# electrosteel2020_10_arrange7_synthboards.net
KiCad netlist of a schematic drawn in EAGLE
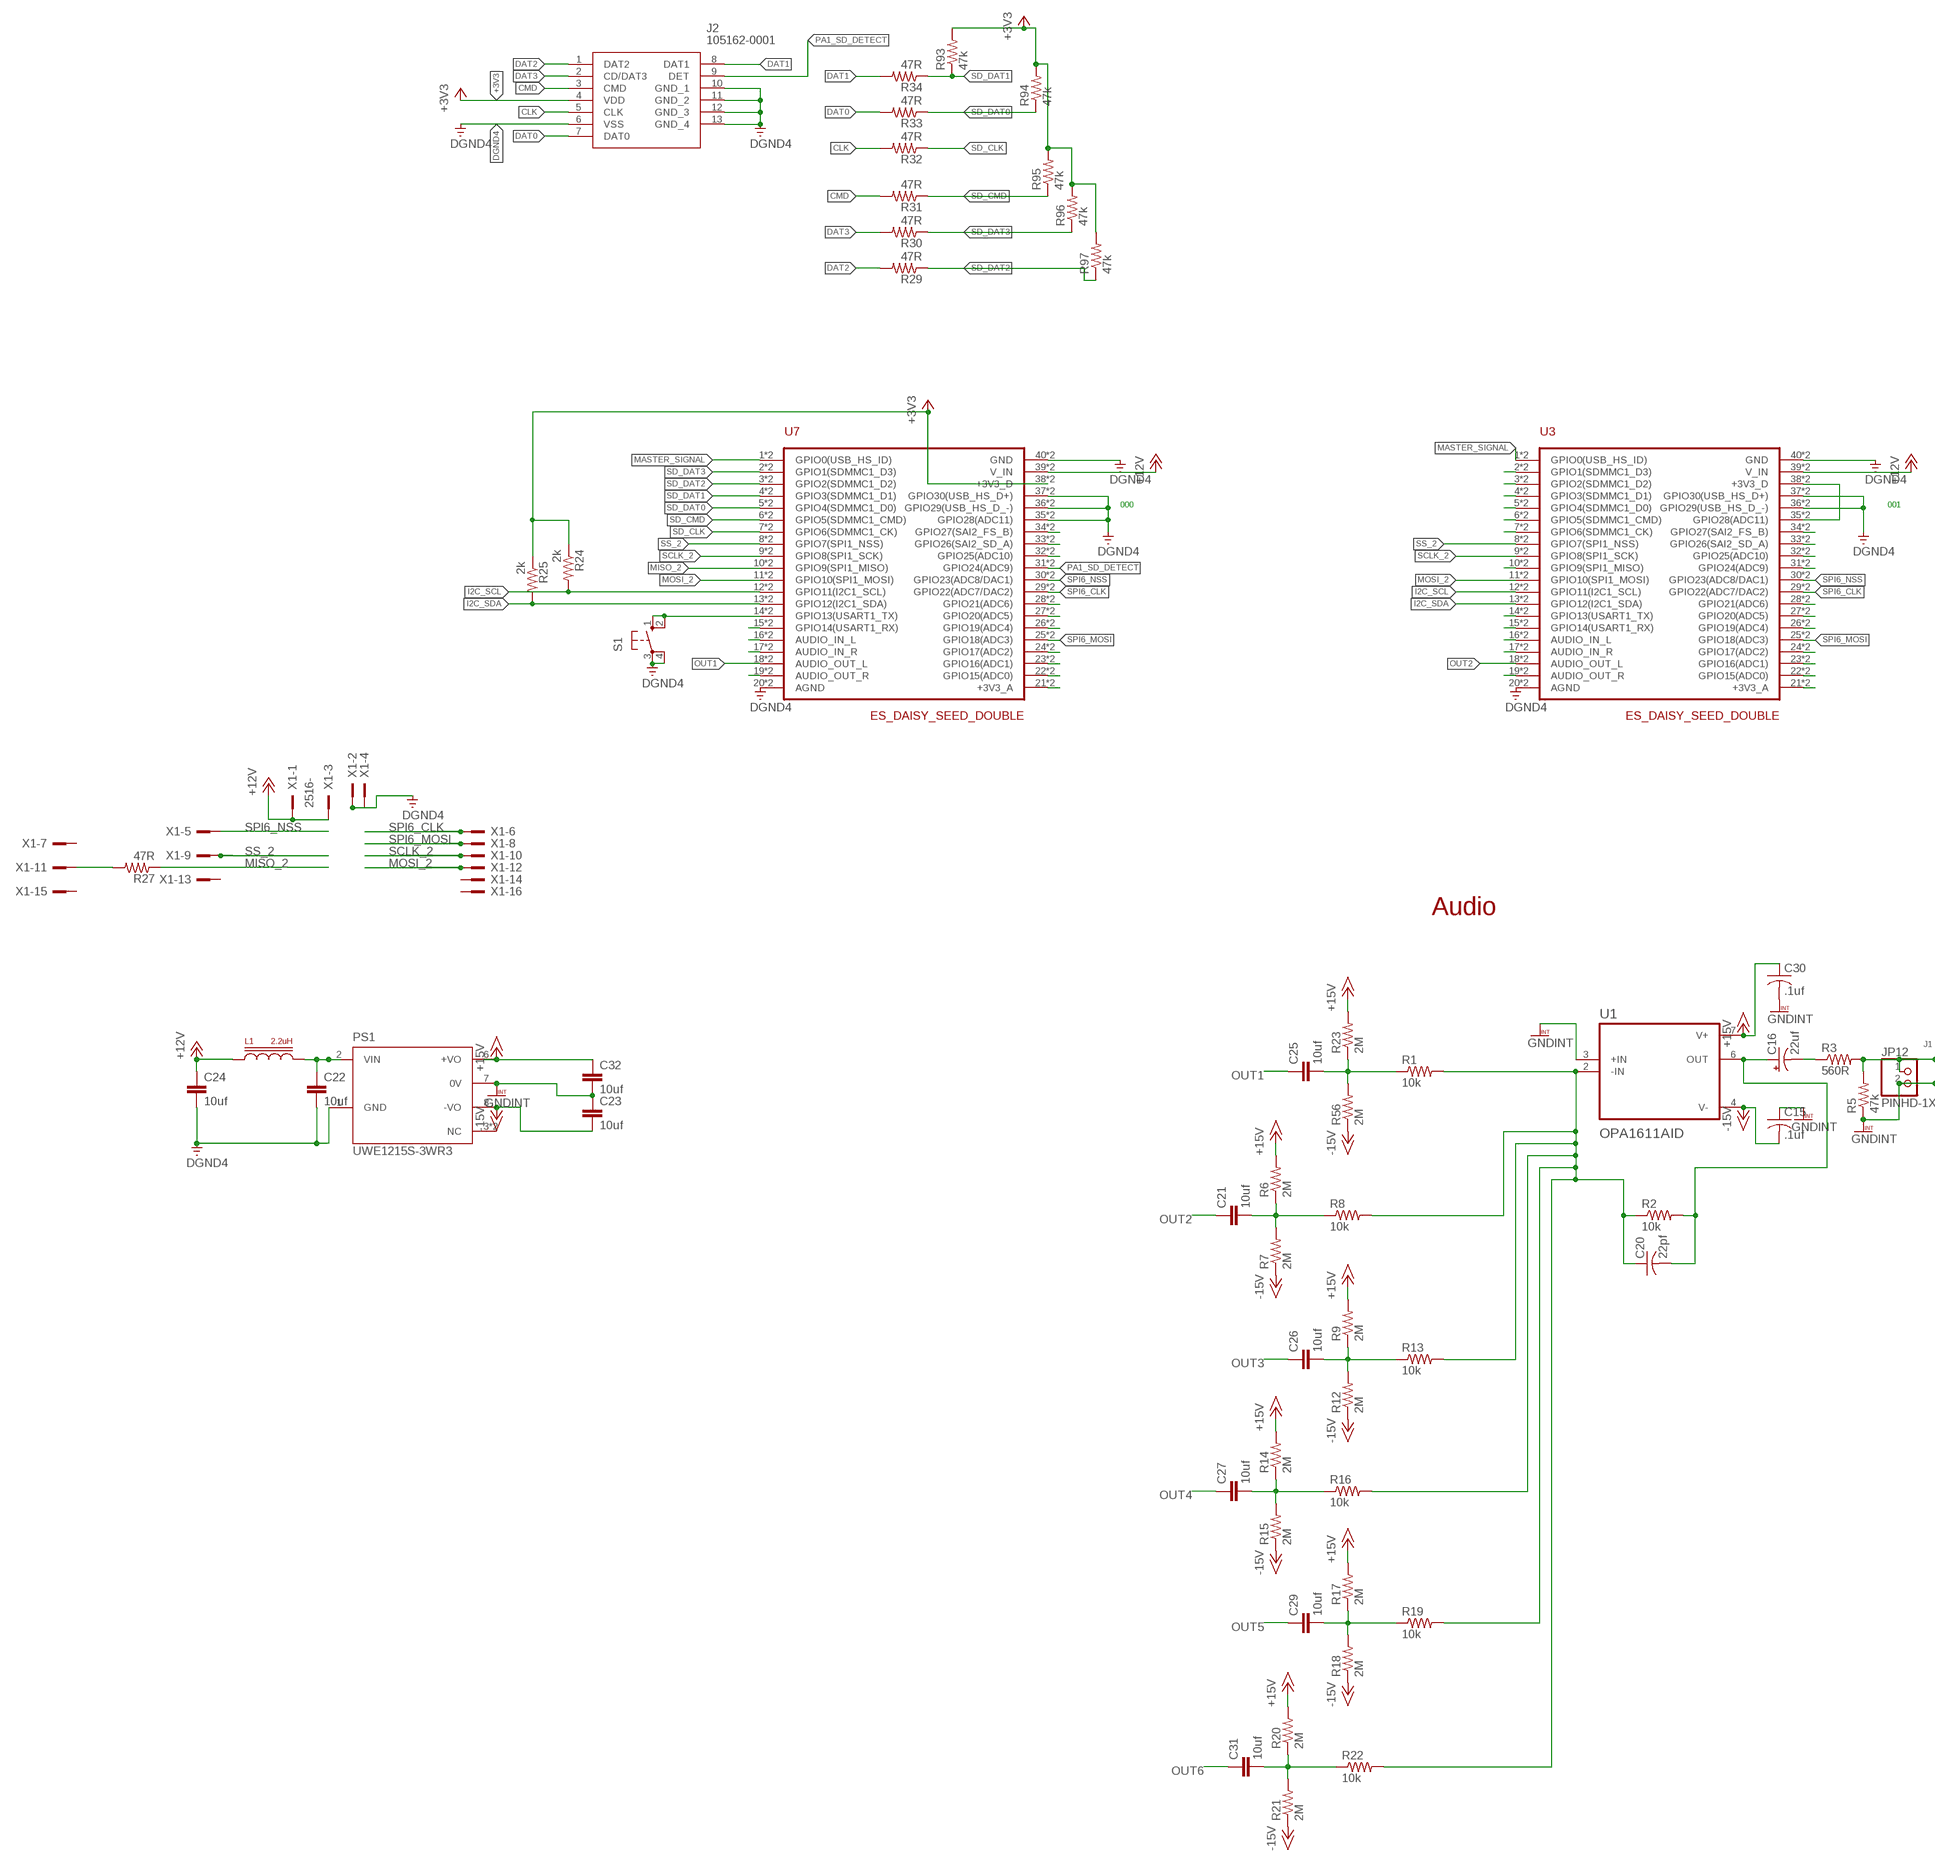
[diagram p0: schematic, sheet 1, part 1 of 3]
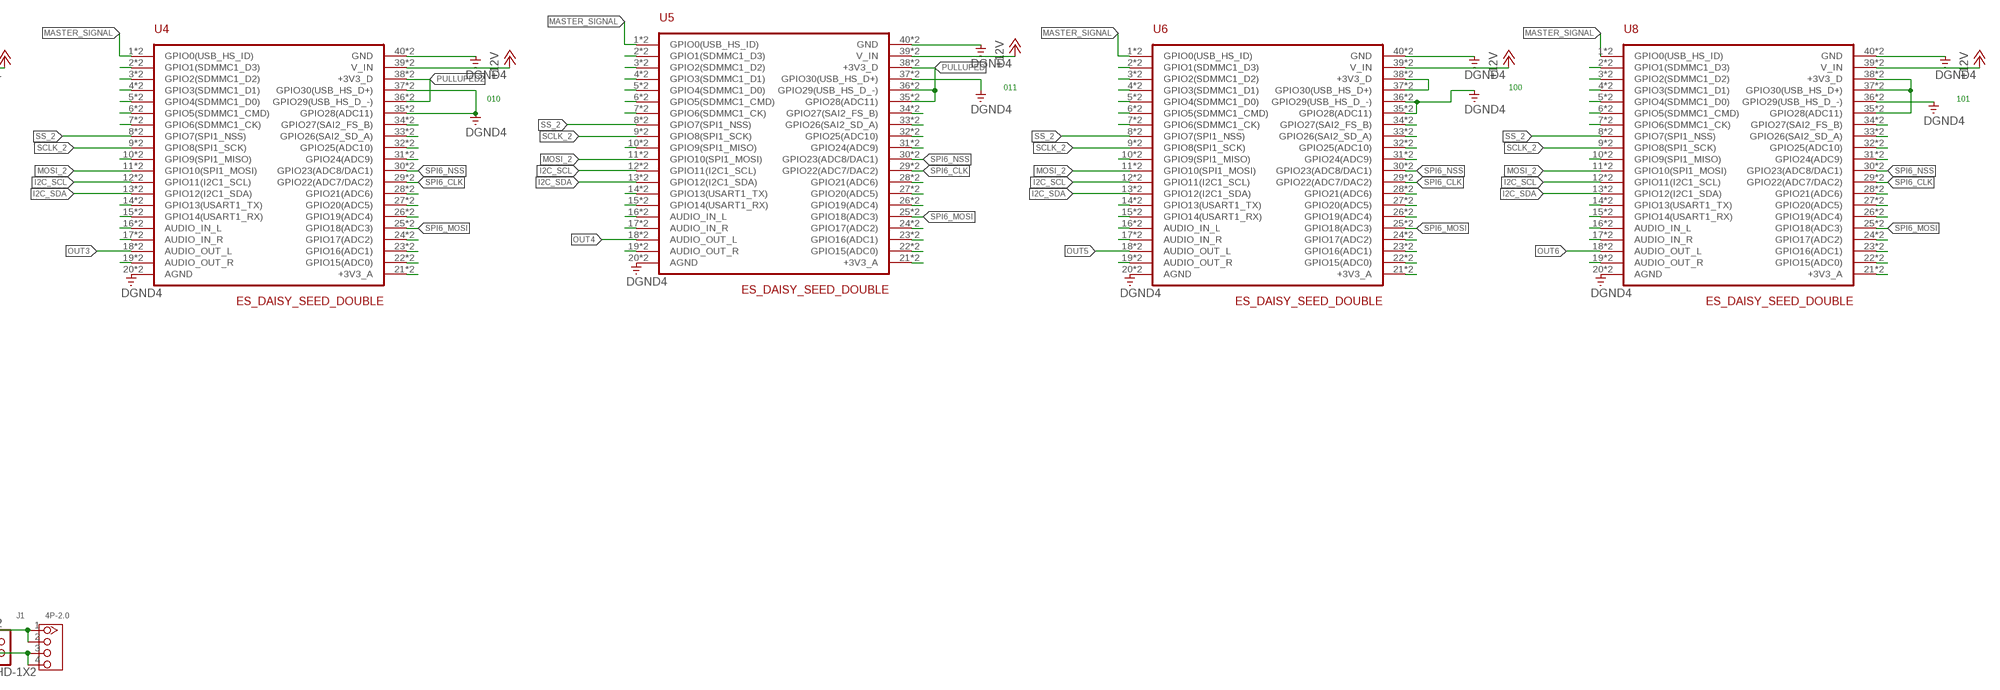
[diagram p1: schematic, sheet 1, part 2 of 3]
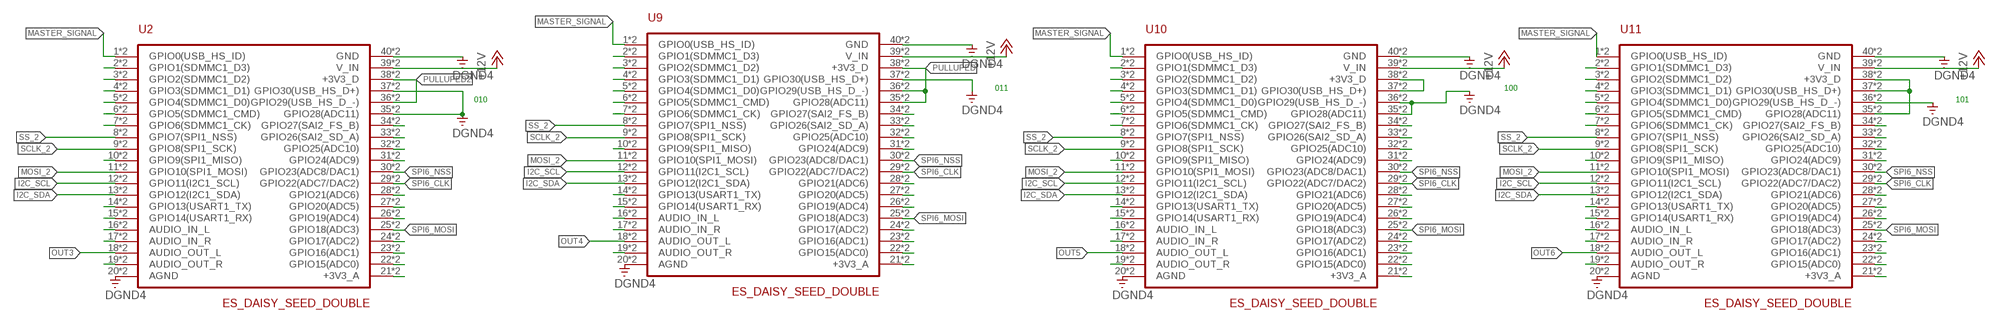
[diagram p2: schematic, sheet 1, part 3 of 3]

(export (version "E")
  (design (tool "Eeschema 10.0.6"))
  (components
    (comp (ref "C15")
      (value ".1uf")
      (footprint "eagle-import:C0603K")
      (fields (field (name "PARTNO") "CC0603KRX7R8BB104"))
      (libsource (lib "eagle-import") (part "C-USC0603K"))
    )
    (comp (ref "C16")
      (value "22uf")
      (footprint "eagle-import:PANASONIC_D")
      (fields (field (name "PARTNO") "EEE-1CA220NP"))
      (libsource (lib "eagle-import") (part "CPOL-USD"))
    )
    (comp (ref "C20")
      (value "22pf")
      (footprint "eagle-import:C0603")
      (fields (field (name "PARTNO") "CC0603JRNPO9BN220"))
      (libsource (lib "eagle-import") (part "rcl_334_C-USC0603"))
    )
    (comp (ref "C21")
      (value "10uf")
      (footprint "eagle-import:C1206K")
      (fields (field (name "PARTNO") "TMK316F106ZL-T"))
      (libsource (lib "eagle-import") (part "C-EUC1206K"))
    )
    (comp (ref "C22")
      (value "10uf")
      (footprint "eagle-import:C1206K")
      (fields (field (name "PARTNO") "TMK316F106ZL-T"))
      (libsource (lib "eagle-import") (part "C-EUC1206K"))
    )
    (comp (ref "C23")
      (value "10uf")
      (footprint "eagle-import:C1206K")
      (fields (field (name "PARTNO") "TMK316F106ZL-T"))
      (libsource (lib "eagle-import") (part "C-EUC1206K"))
    )
    (comp (ref "C24")
      (value "10uf")
      (footprint "eagle-import:C1206K")
      (fields (field (name "PARTNO") "TMK316F106ZL-T"))
      (libsource (lib "eagle-import") (part "C-EUC1206K"))
    )
    (comp (ref "C25")
      (value "10uf")
      (footprint "eagle-import:C1206K")
      (fields (field (name "PARTNO") "TMK316F106ZL-T"))
      (libsource (lib "eagle-import") (part "C-EUC1206K"))
    )
    (comp (ref "C26")
      (value "10uf")
      (footprint "eagle-import:C1206K")
      (fields (field (name "PARTNO") "TMK316F106ZL-T"))
      (libsource (lib "eagle-import") (part "C-EUC1206K"))
    )
    (comp (ref "C27")
      (value "10uf")
      (footprint "eagle-import:C1206K")
      (fields (field (name "PARTNO") "TMK316F106ZL-T"))
      (libsource (lib "eagle-import") (part "C-EUC1206K"))
    )
    (comp (ref "C29")
      (value "10uf")
      (footprint "eagle-import:C1206K")
      (fields (field (name "PARTNO") "TMK316F106ZL-T"))
      (libsource (lib "eagle-import") (part "C-EUC1206K"))
    )
    (comp (ref "C30")
      (value ".1uf")
      (footprint "eagle-import:C0603K")
      (fields (field (name "PARTNO") "CC0603KRX7R8BB104"))
      (libsource (lib "eagle-import") (part "C-USC0603K"))
    )
    (comp (ref "C31")
      (value "10uf")
      (footprint "eagle-import:C1206K")
      (fields (field (name "PARTNO") "TMK316F106ZL-T"))
      (libsource (lib "eagle-import") (part "C-EUC1206K"))
    )
    (comp (ref "C32")
      (value "10uf")
      (footprint "eagle-import:C1206K")
      (fields (field (name "PARTNO") "TMK316F106ZL-T"))
      (libsource (lib "eagle-import") (part "C-EUC1206K"))
    )
    (comp (ref "J1")
      (value "4P-2.0")
      (footprint "eagle-import:HW4-2.0")
      (fields (field (name "PARTNO") "110990030"))
      (libsource (lib "eagle-import") (part "GROVE-CONNECTOR-DIP(4P-2.0)"))
    )
    (comp (ref "J2")
      (value "105162-0001")
      (footprint "eagle-import:105162-0001")
      (fields (field (name "MF") "Molex") (field (name "MP") "1051620001"))
      (libsource (lib "eagle-import") (part "105162-0001"))
    )
    (comp (ref "JP12")
      (value "PINHD-1X2")
      (footprint "eagle-import:1X02")
      (fields (field (name "PARTNO") "*DNP"))
      (libsource (lib "eagle-import") (part "PINHD-1X2"))
    )
    (comp (ref "L1")
      (value "2.2uH")
      (footprint "eagle-import:BOURNS_SRP2010")
      (fields (field (name "PARTNO") "SRP2010-2R2M"))
      (libsource (lib "eagle-import") (part "INDUCTORS"))
    )
    (comp (ref "PS1")
      (value "UWE1215S-3WR3")
      (footprint "eagle-import:CONV_UWE1215S-3WR3")
      (fields
        (field (name "DIGI-KEY_PART_NUMBER") "2725-UWE1215S-3WR3-ND")
        (field (name "MF") "Mornsun America, LLC")
      )
      (libsource (lib "eagle-import") (part "UWE1215S-3WR3"))
    )
    (comp (ref "R1")
      (value "10k")
      (footprint "eagle-import:R0603")
      (fields (field (name "PARTNO") "ESR03EZPF1002"))
      (libsource (lib "eagle-import") (part "Resistor_16378527_R-US_R0603"))
    )
    (comp (ref "R2")
      (value "10k")
      (footprint "eagle-import:R0603")
      (fields (field (name "PARTNO") "ESR03EZPF1002"))
      (libsource (lib "eagle-import") (part "Resistor_16378527_R-US_R0603"))
    )
    (comp (ref "R3")
      (value "560R")
      (footprint "eagle-import:R0603")
      (fields (field (name "PARTNO") "ESR03EZPF5600"))
      (libsource (lib "eagle-import") (part "Resistor_16378527_R-US_R0603"))
    )
    (comp (ref "R5")
      (value "47k")
      (footprint "eagle-import:R0603")
      (fields (field (name "PARTNO") "ESR03EZPJ473"))
      (libsource (lib "eagle-import") (part "Resistor_16378527_R-US_R0603"))
    )
    (comp (ref "R6")
      (value "2M")
      (footprint "eagle-import:R0603")
      (fields (field (name "PARTNO") "RMCF0603FT2M00"))
      (libsource (lib "eagle-import") (part "R-US_R0603"))
    )
    (comp (ref "R7")
      (value "2M")
      (footprint "eagle-import:R0603")
      (fields (field (name "PARTNO") "RMCF0603FT2M00"))
      (libsource (lib "eagle-import") (part "R-US_R0603"))
    )
    (comp (ref "R8")
      (value "10k")
      (footprint "eagle-import:R0603")
      (fields (field (name "PARTNO") "ESR03EZPF1002"))
      (libsource (lib "eagle-import") (part "Resistor_16378527_R-US_R0603"))
    )
    (comp (ref "R9")
      (value "2M")
      (footprint "eagle-import:R0603")
      (fields (field (name "PARTNO") "RMCF0603FT2M00"))
      (libsource (lib "eagle-import") (part "R-US_R0603"))
    )
    (comp (ref "R12")
      (value "2M")
      (footprint "eagle-import:R0603")
      (fields (field (name "PARTNO") "RMCF0603FT2M00"))
      (libsource (lib "eagle-import") (part "R-US_R0603"))
    )
    (comp (ref "R13")
      (value "10k")
      (footprint "eagle-import:R0603")
      (fields (field (name "PARTNO") "ESR03EZPF1002"))
      (libsource (lib "eagle-import") (part "Resistor_16378527_R-US_R0603"))
    )
    (comp (ref "R14")
      (value "2M")
      (footprint "eagle-import:R0603")
      (fields (field (name "PARTNO") "RMCF0603FT2M00"))
      (libsource (lib "eagle-import") (part "R-US_R0603"))
    )
    (comp (ref "R15")
      (value "2M")
      (footprint "eagle-import:R0603")
      (fields (field (name "PARTNO") "RMCF0603FT2M00"))
      (libsource (lib "eagle-import") (part "R-US_R0603"))
    )
    (comp (ref "R16")
      (value "10k")
      (footprint "eagle-import:R0603")
      (fields (field (name "PARTNO") "ESR03EZPF1002"))
      (libsource (lib "eagle-import") (part "Resistor_16378527_R-US_R0603"))
    )
    (comp (ref "R17")
      (value "2M")
      (footprint "eagle-import:R0603")
      (fields (field (name "PARTNO") "RMCF0603FT2M00"))
      (libsource (lib "eagle-import") (part "R-US_R0603"))
    )
    (comp (ref "R18")
      (value "2M")
      (footprint "eagle-import:R0603")
      (fields (field (name "PARTNO") "RMCF0603FT2M00"))
      (libsource (lib "eagle-import") (part "R-US_R0603"))
    )
    (comp (ref "R19")
      (value "10k")
      (footprint "eagle-import:R0603")
      (fields (field (name "PARTNO") "ESR03EZPF1002"))
      (libsource (lib "eagle-import") (part "Resistor_16378527_R-US_R0603"))
    )
    (comp (ref "R20")
      (value "2M")
      (footprint "eagle-import:R0603")
      (fields (field (name "PARTNO") "RMCF0603FT2M00"))
      (libsource (lib "eagle-import") (part "R-US_R0603"))
    )
    (comp (ref "R21")
      (value "2M")
      (footprint "eagle-import:R0603")
      (fields (field (name "PARTNO") "RMCF0603FT2M00"))
      (libsource (lib "eagle-import") (part "R-US_R0603"))
    )
    (comp (ref "R22")
      (value "10k")
      (footprint "eagle-import:R0603")
      (fields (field (name "PARTNO") "ESR03EZPF1002"))
      (libsource (lib "eagle-import") (part "Resistor_16378527_R-US_R0603"))
    )
    (comp (ref "R23")
      (value "2M")
      (footprint "eagle-import:R0603")
      (fields (field (name "PARTNO") "RMCF0603FT2M00"))
      (libsource (lib "eagle-import") (part "R-US_R0603"))
    )
    (comp (ref "R24")
      (value "2k")
      (footprint "eagle-import:R0603")
      (fields (field (name "PARTNO") "ERJ-PA3F2001V"))
      (libsource (lib "eagle-import") (part "rcl_334_R-US_R0603"))
    )
    (comp (ref "R25")
      (value "2k")
      (footprint "eagle-import:R0603")
      (fields (field (name "PARTNO") "ERJ-PA3F2001V"))
      (libsource (lib "eagle-import") (part "rcl_334_R-US_R0603"))
    )
    (comp (ref "R27")
      (value "47R")
      (footprint "eagle-import:R0603")
      (fields (field (name "PARTNO") "RC0603JR-0747RL"))
      (libsource (lib "eagle-import") (part "rcl_334_R-US_R0603"))
    )
    (comp (ref "R29")
      (value "47R")
      (footprint "eagle-import:R0603")
      (fields (field (name "PARTNO") "RC0603JR-0747RL"))
      (libsource (lib "eagle-import") (part "rcl_334_R-US_R0603"))
    )
    (comp (ref "R30")
      (value "47R")
      (footprint "eagle-import:R0603")
      (fields (field (name "PARTNO") "RC0603JR-0747RL"))
      (libsource (lib "eagle-import") (part "rcl_334_R-US_R0603"))
    )
    (comp (ref "R31")
      (value "47R")
      (footprint "eagle-import:R0603")
      (fields (field (name "PARTNO") "RC0603JR-0747RL"))
      (libsource (lib "eagle-import") (part "rcl_334_R-US_R0603"))
    )
    (comp (ref "R32")
      (value "47R")
      (footprint "eagle-import:R0603")
      (fields (field (name "PARTNO") "RC0603JR-0747RL"))
      (libsource (lib "eagle-import") (part "rcl_334_R-US_R0603"))
    )
    (comp (ref "R33")
      (value "47R")
      (footprint "eagle-import:R0603")
      (fields (field (name "PARTNO") "RC0603JR-0747RL"))
      (libsource (lib "eagle-import") (part "rcl_334_R-US_R0603"))
    )
    (comp (ref "R34")
      (value "47R")
      (footprint "eagle-import:R0603")
      (fields (field (name "PARTNO") "RC0603JR-0747RL"))
      (libsource (lib "eagle-import") (part "rcl_334_R-US_R0603"))
    )
    (comp (ref "R56")
      (value "2M")
      (footprint "eagle-import:R0603")
      (fields (field (name "PARTNO") "RMCF0603FT2M00"))
      (libsource (lib "eagle-import") (part "R-US_R0603"))
    )
    (comp (ref "R93")
      (value "47k")
      (footprint "eagle-import:R0603")
      (fields (field (name "PARTNO") "ESR03EZPJ473"))
      (libsource (lib "eagle-import") (part "rcl_R-US_R0603"))
    )
    (comp (ref "R94")
      (value "47k")
      (footprint "eagle-import:R0603")
      (fields (field (name "PARTNO") "ESR03EZPJ473"))
      (libsource (lib "eagle-import") (part "rcl_R-US_R0603"))
    )
    (comp (ref "R95")
      (value "47k")
      (footprint "eagle-import:R0603")
      (fields (field (name "PARTNO") "ESR03EZPJ473"))
      (libsource (lib "eagle-import") (part "rcl_R-US_R0603"))
    )
    (comp (ref "R96")
      (value "47k")
      (footprint "eagle-import:R0603")
      (fields (field (name "PARTNO") "ESR03EZPJ473"))
      (libsource (lib "eagle-import") (part "rcl_R-US_R0603"))
    )
    (comp (ref "R97")
      (value "47k")
      (footprint "eagle-import:R0603")
      (fields (field (name "PARTNO") "ESR03EZPJ473"))
      (libsource (lib "eagle-import") (part "rcl_R-US_R0603"))
    )
    (comp (ref "S1")
      (value "10-XX")
      (footprint "eagle-import:B3F-10XX")
      (fields (field (name "MPN") "B3F-1000"))
      (libsource (lib "eagle-import") (part "10-XX"))
    )
    (comp (ref "U1")
      (value "OPA1611AID")
      (footprint "eagle-import:SOIC127P599X175-8N")
      (fields (field (name "DIGI-KEY_PART_NUMBER") "296-24958-5-ND") (field (name "MF") "Texas Instruments"))
      (libsource (lib "eagle-import") (part "OPA1611AID"))
    )
    (comp (ref "U2")
      (value "ES_DAISY_SEED_DOUBLE")
      (footprint "eagle-import:ES_DAISY_SEED_DOUBLE")
      (fields (field (name "PARTNO") "4840-6004-CP"))
      (libsource (lib "eagle-import") (part "ES_DAISY_SEED_DOUBLE"))
    )
    (comp (ref "U3")
      (value "ES_DAISY_SEED_DOUBLE")
      (footprint "eagle-import:ES_DAISY_SEED_DOUBLE")
      (fields (field (name "PARTNO") "4840-6004-CP"))
      (libsource (lib "eagle-import") (part "ES_DAISY_SEED_DOUBLE"))
    )
    (comp (ref "U4")
      (value "ES_DAISY_SEED_DOUBLE")
      (footprint "eagle-import:ES_DAISY_SEED_DOUBLE")
      (fields (field (name "PARTNO") "4840-6004-CP"))
      (libsource (lib "eagle-import") (part "ES_DAISY_SEED_DOUBLE"))
    )
    (comp (ref "U5")
      (value "ES_DAISY_SEED_DOUBLE")
      (footprint "eagle-import:ES_DAISY_SEED_DOUBLE")
      (fields (field (name "PARTNO") "4840-6004-CP"))
      (libsource (lib "eagle-import") (part "ES_DAISY_SEED_DOUBLE"))
    )
    (comp (ref "U6")
      (value "ES_DAISY_SEED_DOUBLE")
      (footprint "eagle-import:ES_DAISY_SEED_DOUBLE")
      (fields (field (name "PARTNO") "4840-6004-CP"))
      (libsource (lib "eagle-import") (part "ES_DAISY_SEED_DOUBLE"))
    )
    (comp (ref "U7")
      (value "ES_DAISY_SEED_DOUBLE")
      (footprint "eagle-import:ES_DAISY_SEED_DOUBLE")
      (fields (field (name "PARTNO") "4840-6004-CP"))
      (libsource (lib "eagle-import") (part "ES_DAISY_SEED_DOUBLE"))
    )
    (comp (ref "U8")
      (value "ES_DAISY_SEED_DOUBLE")
      (footprint "eagle-import:ES_DAISY_SEED_DOUBLE")
      (fields (field (name "PARTNO") "4840-6004-CP"))
      (libsource (lib "eagle-import") (part "ES_DAISY_SEED_DOUBLE"))
    )
    (comp (ref "U9")
      (value "ES_DAISY_SEED_DOUBLE")
      (footprint "eagle-import:ES_DAISY_SEED_DOUBLE")
      (fields (field (name "PARTNO") "4840-6004-CP"))
      (libsource (lib "eagle-import") (part "ES_DAISY_SEED_DOUBLE"))
    )
    (comp (ref "U10")
      (value "ES_DAISY_SEED_DOUBLE")
      (footprint "eagle-import:ES_DAISY_SEED_DOUBLE")
      (fields (field (name "PARTNO") "4840-6004-CP"))
      (libsource (lib "eagle-import") (part "ES_DAISY_SEED_DOUBLE"))
    )
    (comp (ref "U11")
      (value "ES_DAISY_SEED_DOUBLE")
      (footprint "eagle-import:ES_DAISY_SEED_DOUBLE")
      (fields (field (name "PARTNO") "4840-6004-CP"))
      (libsource (lib "eagle-import") (part "ES_DAISY_SEED_DOUBLE"))
    )
    (comp (ref "X1")
      (value "2516-")
      (footprint "eagle-import:PAK100_2500-16")
      (fields (field (name "PARTNO") "SBH11-PBPC-D08-ST-BK"))
      (libsource (lib "eagle-import") (part "2516-"))
    )
  )
  (nets
    (net (code "1") (name "+3V3") (class "Default")
      (node (ref "J2") (pin "4") (pinfunction "VDD_4") (pintype "bidirectional"))
      (node (ref "R24") (pin "1") (pinfunction "1_1") (pintype "passive"))
      (node (ref "R25") (pin "1") (pinfunction "1_1") (pintype "passive"))
      (node (ref "R93") (pin "2") (pinfunction "2_2") (pintype "passive"))
      (node (ref "R94") (pin "2") (pinfunction "2_2") (pintype "passive"))
      (node (ref "R95") (pin "2") (pinfunction "2_2") (pintype "passive"))
      (node (ref "R96") (pin "2") (pinfunction "2_2") (pintype "passive"))
      (node (ref "R97") (pin "2") (pinfunction "2_2") (pintype "passive"))
      (node (ref "U7") (pin "38") (pinfunction "+3V3_D_38") (pintype "bidirectional"))
      (node (ref "U7") (pin "B38") (pinfunction "+3V3_D_B38") (pintype "bidirectional"))
    )
    (net (code "2") (name "+12V") (class "Default")
      (node (ref "C24") (pin "1") (pinfunction "1_1") (pintype "passive"))
      (node (ref "L1") (pin "P$1") (pinfunction "P$1_P$1") (pintype "bidirectional"))
      (node (ref "U10") (pin "39") (pinfunction "V_IN_39") (pintype "bidirectional"))
      (node (ref "U10") (pin "B39") (pinfunction "V_IN_B39") (pintype "bidirectional"))
      (node (ref "U11") (pin "39") (pinfunction "V_IN_39") (pintype "bidirectional"))
      (node (ref "U11") (pin "B39") (pinfunction "V_IN_B39") (pintype "bidirectional"))
      (node (ref "U2") (pin "39") (pinfunction "V_IN_39") (pintype "bidirectional"))
      (node (ref "U2") (pin "B39") (pinfunction "V_IN_B39") (pintype "bidirectional"))
      (node (ref "U3") (pin "39") (pinfunction "V_IN_39") (pintype "bidirectional"))
      (node (ref "U3") (pin "B39") (pinfunction "V_IN_B39") (pintype "bidirectional"))
      (node (ref "U4") (pin "39") (pinfunction "V_IN_39") (pintype "bidirectional"))
      (node (ref "U4") (pin "B39") (pinfunction "V_IN_B39") (pintype "bidirectional"))
      (node (ref "U5") (pin "39") (pinfunction "V_IN_39") (pintype "bidirectional"))
      (node (ref "U5") (pin "B39") (pinfunction "V_IN_B39") (pintype "bidirectional"))
      (node (ref "U6") (pin "39") (pinfunction "V_IN_39") (pintype "bidirectional"))
      (node (ref "U6") (pin "B39") (pinfunction "V_IN_B39") (pintype "bidirectional"))
      (node (ref "U7") (pin "39") (pinfunction "V_IN_39") (pintype "bidirectional"))
      (node (ref "U7") (pin "B39") (pinfunction "V_IN_B39") (pintype "bidirectional"))
      (node (ref "U8") (pin "39") (pinfunction "V_IN_39") (pintype "bidirectional"))
      (node (ref "U8") (pin "B39") (pinfunction "V_IN_B39") (pintype "bidirectional"))
      (node (ref "U9") (pin "39") (pinfunction "V_IN_39") (pintype "bidirectional"))
      (node (ref "U9") (pin "B39") (pinfunction "V_IN_B39") (pintype "bidirectional"))
      (node (ref "X1") (pin "1") (pinfunction "KL_1") (pintype "passive"))
      (node (ref "X1") (pin "3") (pinfunction "KL_3") (pintype "passive"))
    )
    (net (code "3") (name "+15V") (class "Default")
      (node (ref "C30") (pin "1") (pinfunction "1_1") (pintype "passive"))
      (node (ref "C32") (pin "1") (pinfunction "1_1") (pintype "passive"))
      (node (ref "PS1") (pin "6") (pinfunction "+VO_6") (pintype "output"))
      (node (ref "R14") (pin "2") (pinfunction "2_2") (pintype "passive"))
      (node (ref "R17") (pin "2") (pinfunction "2_2") (pintype "passive"))
      (node (ref "R20") (pin "2") (pinfunction "2_2") (pintype "passive"))
      (node (ref "R23") (pin "2") (pinfunction "2_2") (pintype "passive"))
      (node (ref "R6") (pin "2") (pinfunction "2_2") (pintype "passive"))
      (node (ref "R9") (pin "2") (pinfunction "2_2") (pintype "passive"))
      (node (ref "U1") (pin "7") (pinfunction "V+_7") (pintype "power_in"))
    )
    (net (code "4") (name "-15V") (class "Default")
      (node (ref "C15") (pin "2") (pinfunction "2_2") (pintype "passive"))
      (node (ref "C23") (pin "2") (pinfunction "2_2") (pintype "passive"))
      (node (ref "PS1") (pin "8") (pinfunction "-VO_8") (pintype "output"))
      (node (ref "R12") (pin "1") (pinfunction "1_1") (pintype "passive"))
      (node (ref "R15") (pin "1") (pinfunction "1_1") (pintype "passive"))
      (node (ref "R18") (pin "1") (pinfunction "1_1") (pintype "passive"))
      (node (ref "R21") (pin "1") (pinfunction "1_1") (pintype "passive"))
      (node (ref "R56") (pin "1") (pinfunction "1_1") (pintype "passive"))
      (node (ref "R7") (pin "1") (pinfunction "1_1") (pintype "passive"))
      (node (ref "U1") (pin "4") (pinfunction "V-_4") (pintype "power_in"))
    )
    (net (code "5") (name "CLK") (class "Default")
      (node (ref "J2") (pin "5") (pinfunction "CLK_5") (pintype "bidirectional"))
      (node (ref "R32") (pin "2") (pinfunction "2_2") (pintype "passive"))
    )
    (net (code "6") (name "CMD") (class "Default")
      (node (ref "J2") (pin "3") (pinfunction "CMD_3") (pintype "bidirectional"))
      (node (ref "R31") (pin "2") (pinfunction "2_2") (pintype "passive"))
    )
    (net (code "7") (name "DAT0") (class "Default")
      (node (ref "J2") (pin "7") (pinfunction "DAT0_7") (pintype "bidirectional"))
      (node (ref "R33") (pin "2") (pinfunction "2_2") (pintype "passive"))
    )
    (net (code "8") (name "DAT1") (class "Default")
      (node (ref "J2") (pin "8") (pinfunction "DAT1_8") (pintype "bidirectional"))
      (node (ref "R34") (pin "2") (pinfunction "2_2") (pintype "passive"))
    )
    (net (code "9") (name "DAT2") (class "Default")
      (node (ref "J2") (pin "1") (pinfunction "DAT2_1") (pintype "bidirectional"))
      (node (ref "R29") (pin "2") (pinfunction "2_2") (pintype "passive"))
    )
    (net (code "10") (name "DAT3") (class "Default")
      (node (ref "J2") (pin "2") (pinfunction "CD/DAT3_2") (pintype "bidirectional"))
      (node (ref "R30") (pin "2") (pinfunction "2_2") (pintype "passive"))
    )
    (net (code "11") (name "DGND4") (class "Default")
      (node (ref "C22") (pin "2") (pinfunction "2_2") (pintype "passive"))
      (node (ref "C24") (pin "2") (pinfunction "2_2") (pintype "passive"))
      (node (ref "J2") (pin "10") (pinfunction "GND_1_10") (pintype "bidirectional"))
      (node (ref "J2") (pin "11") (pinfunction "GND_2_11") (pintype "bidirectional"))
      (node (ref "J2") (pin "12") (pinfunction "GND_3_12") (pintype "bidirectional"))
      (node (ref "J2") (pin "13") (pinfunction "GND_4_13") (pintype "bidirectional"))
      (node (ref "J2") (pin "6") (pinfunction "VSS_6") (pintype "bidirectional"))
      (node (ref "PS1") (pin "1") (pinfunction "GND_1") (pintype "power_in"))
      (node (ref "S1") (pin "3") (pinfunction "P_3") (pintype "passive"))
      (node (ref "S1") (pin "4") (pinfunction "P1_4") (pintype "passive"))
      (node (ref "U10") (pin "20") (pinfunction "AGND_20") (pintype "bidirectional"))
      (node (ref "U10") (pin "35") (pinfunction "GPIO28(ADC11)_35") (pintype "bidirectional"))
      (node (ref "U10") (pin "36") (pinfunction "GPIO29(USB_HS_D_-)_36") (pintype "bidirectional"))
      (node (ref "U10") (pin "40") (pinfunction "GND_40") (pintype "bidirectional"))
      (node (ref "U10") (pin "B20") (pinfunction "AGND_B20") (pintype "bidirectional"))
      (node (ref "U10") (pin "B35") (pinfunction "GPIO28(ADC11)_B35") (pintype "bidirectional"))
      (node (ref "U10") (pin "B36") (pinfunction "GPIO29(USB_HS_D_-)_B36") (pintype "bidirectional"))
      (node (ref "U10") (pin "B40") (pinfunction "GND_B40") (pintype "bidirectional"))
      (node (ref "U11") (pin "20") (pinfunction "AGND_20") (pintype "bidirectional"))
      (node (ref "U11") (pin "36") (pinfunction "GPIO29(USB_HS_D_-)_36") (pintype "bidirectional"))
      (node (ref "U11") (pin "40") (pinfunction "GND_40") (pintype "bidirectional"))
      (node (ref "U11") (pin "B20") (pinfunction "AGND_B20") (pintype "bidirectional"))
      (node (ref "U11") (pin "B36") (pinfunction "GPIO29(USB_HS_D_-)_B36") (pintype "bidirectional"))
      (node (ref "U11") (pin "B40") (pinfunction "GND_B40") (pintype "bidirectional"))
      (node (ref "U2") (pin "20") (pinfunction "AGND_20") (pintype "bidirectional"))
      (node (ref "U2") (pin "35") (pinfunction "GPIO28(ADC11)_35") (pintype "bidirectional"))
      (node (ref "U2") (pin "37") (pinfunction "GPIO30(USB_HS_D+)_37") (pintype "bidirectional"))
      (node (ref "U2") (pin "40") (pinfunction "GND_40") (pintype "bidirectional"))
      (node (ref "U2") (pin "B20") (pinfunction "AGND_B20") (pintype "bidirectional"))
      (node (ref "U2") (pin "B35") (pinfunction "GPIO28(ADC11)_B35") (pintype "bidirectional"))
      (node (ref "U2") (pin "B37") (pinfunction "GPIO30(USB_HS_D+)_B37") (pintype "bidirectional"))
      (node (ref "U2") (pin "B40") (pinfunction "GND_B40") (pintype "bidirectional"))
      (node (ref "U3") (pin "20") (pinfunction "AGND_20") (pintype "bidirectional"))
      (node (ref "U3") (pin "36") (pinfunction "GPIO29(USB_HS_D_-)_36") (pintype "bidirectional"))
      (node (ref "U3") (pin "37") (pinfunction "GPIO30(USB_HS_D+)_37") (pintype "bidirectional"))
      (node (ref "U3") (pin "40") (pinfunction "GND_40") (pintype "bidirectional"))
      (node (ref "U3") (pin "B20") (pinfunction "AGND_B20") (pintype "bidirectional"))
      (node (ref "U3") (pin "B36") (pinfunction "GPIO29(USB_HS_D_-)_B36") (pintype "bidirectional"))
      (node (ref "U3") (pin "B37") (pinfunction "GPIO30(USB_HS_D+)_B37") (pintype "bidirectional"))
      (node (ref "U3") (pin "B40") (pinfunction "GND_B40") (pintype "bidirectional"))
      (node (ref "U4") (pin "20") (pinfunction "AGND_20") (pintype "bidirectional"))
      (node (ref "U4") (pin "35") (pinfunction "GPIO28(ADC11)_35") (pintype "bidirectional"))
      (node (ref "U4") (pin "37") (pinfunction "GPIO30(USB_HS_D+)_37") (pintype "bidirectional"))
      (node (ref "U4") (pin "40") (pinfunction "GND_40") (pintype "bidirectional"))
      (node (ref "U4") (pin "B20") (pinfunction "AGND_B20") (pintype "bidirectional"))
      (node (ref "U4") (pin "B35") (pinfunction "GPIO28(ADC11)_B35") (pintype "bidirectional"))
      (node (ref "U4") (pin "B37") (pinfunction "GPIO30(USB_HS_D+)_B37") (pintype "bidirectional"))
      (node (ref "U4") (pin "B40") (pinfunction "GND_B40") (pintype "bidirectional"))
      (node (ref "U5") (pin "20") (pinfunction "AGND_20") (pintype "bidirectional"))
      (node (ref "U5") (pin "37") (pinfunction "GPIO30(USB_HS_D+)_37") (pintype "bidirectional"))
      (node (ref "U5") (pin "40") (pinfunction "GND_40") (pintype "bidirectional"))
      (node (ref "U5") (pin "B20") (pinfunction "AGND_B20") (pintype "bidirectional"))
      (node (ref "U5") (pin "B37") (pinfunction "GPIO30(USB_HS_D+)_B37") (pintype "bidirectional"))
      (node (ref "U5") (pin "B40") (pinfunction "GND_B40") (pintype "bidirectional"))
      (node (ref "U6") (pin "20") (pinfunction "AGND_20") (pintype "bidirectional"))
      (node (ref "U6") (pin "35") (pinfunction "GPIO28(ADC11)_35") (pintype "bidirectional"))
      (node (ref "U6") (pin "36") (pinfunction "GPIO29(USB_HS_D_-)_36") (pintype "bidirectional"))
      (node (ref "U6") (pin "40") (pinfunction "GND_40") (pintype "bidirectional"))
      (node (ref "U6") (pin "B20") (pinfunction "AGND_B20") (pintype "bidirectional"))
      (node (ref "U6") (pin "B35") (pinfunction "GPIO28(ADC11)_B35") (pintype "bidirectional"))
      (node (ref "U6") (pin "B36") (pinfunction "GPIO29(USB_HS_D_-)_B36") (pintype "bidirectional"))
      (node (ref "U6") (pin "B40") (pinfunction "GND_B40") (pintype "bidirectional"))
      (node (ref "U7") (pin "20") (pinfunction "AGND_20") (pintype "bidirectional"))
      (node (ref "U7") (pin "35") (pinfunction "GPIO28(ADC11)_35") (pintype "bidirectional"))
      (node (ref "U7") (pin "36") (pinfunction "GPIO29(USB_HS_D_-)_36") (pintype "bidirectional"))
      (node (ref "U7") (pin "37") (pinfunction "GPIO30(USB_HS_D+)_37") (pintype "bidirectional"))
      (node (ref "U7") (pin "40") (pinfunction "GND_40") (pintype "bidirectional"))
      (node (ref "U7") (pin "B20") (pinfunction "AGND_B20") (pintype "bidirectional"))
      (node (ref "U7") (pin "B35") (pinfunction "GPIO28(ADC11)_B35") (pintype "bidirectional"))
      (node (ref "U7") (pin "B36") (pinfunction "GPIO29(USB_HS_D_-)_B36") (pintype "bidirectional"))
      (node (ref "U7") (pin "B37") (pinfunction "GPIO30(USB_HS_D+)_B37") (pintype "bidirectional"))
      (node (ref "U7") (pin "B40") (pinfunction "GND_B40") (pintype "bidirectional"))
      (node (ref "U8") (pin "20") (pinfunction "AGND_20") (pintype "bidirectional"))
      (node (ref "U8") (pin "36") (pinfunction "GPIO29(USB_HS_D_-)_36") (pintype "bidirectional"))
      (node (ref "U8") (pin "40") (pinfunction "GND_40") (pintype "bidirectional"))
      (node (ref "U8") (pin "B20") (pinfunction "AGND_B20") (pintype "bidirectional"))
      (node (ref "U8") (pin "B36") (pinfunction "GPIO29(USB_HS_D_-)_B36") (pintype "bidirectional"))
      (node (ref "U8") (pin "B40") (pinfunction "GND_B40") (pintype "bidirectional"))
      (node (ref "U9") (pin "20") (pinfunction "AGND_20") (pintype "bidirectional"))
      (node (ref "U9") (pin "37") (pinfunction "GPIO30(USB_HS_D+)_37") (pintype "bidirectional"))
      (node (ref "U9") (pin "40") (pinfunction "GND_40") (pintype "bidirectional"))
      (node (ref "U9") (pin "B20") (pinfunction "AGND_B20") (pintype "bidirectional"))
      (node (ref "U9") (pin "B37") (pinfunction "GPIO30(USB_HS_D+)_B37") (pintype "bidirectional"))
      (node (ref "U9") (pin "B40") (pinfunction "GND_B40") (pintype "bidirectional"))
      (node (ref "X1") (pin "2") (pinfunction "KL_2") (pintype "passive"))
      (node (ref "X1") (pin "4") (pinfunction "KL_4") (pintype "passive"))
    )
    (net (code "12") (name "GNDINT") (class "Default")
      (node (ref "C15") (pin "1") (pinfunction "1_1") (pintype "passive"))
      (node (ref "C23") (pin "1") (pinfunction "1_1") (pintype "passive"))
      (node (ref "C30") (pin "2") (pinfunction "2_2") (pintype "passive"))
      (node (ref "C32") (pin "2") (pinfunction "2_2") (pintype "passive"))
      (node (ref "J1") (pin "3") (pinfunction "3_3") (pintype "bidirectional"))
      (node (ref "J1") (pin "4") (pinfunction "4_4") (pintype "bidirectional"))
      (node (ref "JP12") (pin "2") (pinfunction "2_2") (pintype "passive"))
      (node (ref "PS1") (pin "7") (pinfunction "0V_7") (pintype "passive"))
      (node (ref "R5") (pin "1") (pinfunction "1_1") (pintype "passive"))
      (node (ref "U1") (pin "3") (pinfunction "+IN_3") (pintype "input"))
    )
    (net (code "13") (name "I2C_SCL") (class "Default")
      (node (ref "R24") (pin "2") (pinfunction "2_2") (pintype "passive"))
      (node (ref "U10") (pin "12") (pinfunction "GPIO11(I2C1_SCL)_12") (pintype "bidirectional"))
      (node (ref "U10") (pin "B12") (pinfunction "GPIO11(I2C1_SCL)_B12") (pintype "bidirectional"))
      (node (ref "U11") (pin "12") (pinfunction "GPIO11(I2C1_SCL)_12") (pintype "bidirectional"))
      (node (ref "U11") (pin "B12") (pinfunction "GPIO11(I2C1_SCL)_B12") (pintype "bidirectional"))
      (node (ref "U2") (pin "12") (pinfunction "GPIO11(I2C1_SCL)_12") (pintype "bidirectional"))
      (node (ref "U2") (pin "B12") (pinfunction "GPIO11(I2C1_SCL)_B12") (pintype "bidirectional"))
      (node (ref "U3") (pin "12") (pinfunction "GPIO11(I2C1_SCL)_12") (pintype "bidirectional"))
      (node (ref "U3") (pin "B12") (pinfunction "GPIO11(I2C1_SCL)_B12") (pintype "bidirectional"))
      (node (ref "U4") (pin "12") (pinfunction "GPIO11(I2C1_SCL)_12") (pintype "bidirectional"))
      (node (ref "U4") (pin "B12") (pinfunction "GPIO11(I2C1_SCL)_B12") (pintype "bidirectional"))
      (node (ref "U5") (pin "12") (pinfunction "GPIO11(I2C1_SCL)_12") (pintype "bidirectional"))
      (node (ref "U5") (pin "B12") (pinfunction "GPIO11(I2C1_SCL)_B12") (pintype "bidirectional"))
      (node (ref "U6") (pin "12") (pinfunction "GPIO11(I2C1_SCL)_12") (pintype "bidirectional"))
      (node (ref "U6") (pin "B12") (pinfunction "GPIO11(I2C1_SCL)_B12") (pintype "bidirectional"))
      (node (ref "U7") (pin "12") (pinfunction "GPIO11(I2C1_SCL)_12") (pintype "bidirectional"))
      (node (ref "U7") (pin "B12") (pinfunction "GPIO11(I2C1_SCL)_B12") (pintype "bidirectional"))
      (node (ref "U8") (pin "12") (pinfunction "GPIO11(I2C1_SCL)_12") (pintype "bidirectional"))
      (node (ref "U8") (pin "B12") (pinfunction "GPIO11(I2C1_SCL)_B12") (pintype "bidirectional"))
      (node (ref "U9") (pin "12") (pinfunction "GPIO11(I2C1_SCL)_12") (pintype "bidirectional"))
      (node (ref "U9") (pin "B12") (pinfunction "GPIO11(I2C1_SCL)_B12") (pintype "bidirectional"))
    )
    (net (code "14") (name "I2C_SDA") (class "Default")
      (node (ref "R25") (pin "2") (pinfunction "2_2") (pintype "passive"))
      (node (ref "U10") (pin "13") (pinfunction "GPIO12(I2C1_SDA)_13") (pintype "bidirectional"))
      (node (ref "U10") (pin "B13") (pinfunction "GPIO12(I2C1_SDA)_B13") (pintype "bidirectional"))
      (node (ref "U11") (pin "13") (pinfunction "GPIO12(I2C1_SDA)_13") (pintype "bidirectional"))
      (node (ref "U11") (pin "B13") (pinfunction "GPIO12(I2C1_SDA)_B13") (pintype "bidirectional"))
      (node (ref "U2") (pin "13") (pinfunction "GPIO12(I2C1_SDA)_13") (pintype "bidirectional"))
      (node (ref "U2") (pin "B13") (pinfunction "GPIO12(I2C1_SDA)_B13") (pintype "bidirectional"))
      (node (ref "U3") (pin "13") (pinfunction "GPIO12(I2C1_SDA)_13") (pintype "bidirectional"))
      (node (ref "U3") (pin "B13") (pinfunction "GPIO12(I2C1_SDA)_B13") (pintype "bidirectional"))
      (node (ref "U4") (pin "13") (pinfunction "GPIO12(I2C1_SDA)_13") (pintype "bidirectional"))
      (node (ref "U4") (pin "B13") (pinfunction "GPIO12(I2C1_SDA)_B13") (pintype "bidirectional"))
      (node (ref "U5") (pin "13") (pinfunction "GPIO12(I2C1_SDA)_13") (pintype "bidirectional"))
      (node (ref "U5") (pin "B13") (pinfunction "GPIO12(I2C1_SDA)_B13") (pintype "bidirectional"))
      (node (ref "U6") (pin "13") (pinfunction "GPIO12(I2C1_SDA)_13") (pintype "bidirectional"))
      (node (ref "U6") (pin "B13") (pinfunction "GPIO12(I2C1_SDA)_B13") (pintype "bidirectional"))
      (node (ref "U7") (pin "13") (pinfunction "GPIO12(I2C1_SDA)_13") (pintype "bidirectional"))
      (node (ref "U7") (pin "B13") (pinfunction "GPIO12(I2C1_SDA)_B13") (pintype "bidirectional"))
      (node (ref "U8") (pin "13") (pinfunction "GPIO12(I2C1_SDA)_13") (pintype "bidirectional"))
      (node (ref "U8") (pin "B13") (pinfunction "GPIO12(I2C1_SDA)_B13") (pintype "bidirectional"))
      (node (ref "U9") (pin "13") (pinfunction "GPIO12(I2C1_SDA)_13") (pintype "bidirectional"))
      (node (ref "U9") (pin "B13") (pinfunction "GPIO12(I2C1_SDA)_B13") (pintype "bidirectional"))
    )
    (net (code "15") (name "MASTER_SIGNAL") (class "Default")
      (node (ref "U10") (pin "1") (pinfunction "GPIO0(USB_HS_ID)_1") (pintype "bidirectional"))
      (node (ref "U10") (pin "B1") (pinfunction "GPIO0(USB_HS_ID)_B1") (pintype "bidirectional"))
      (node (ref "U11") (pin "1") (pinfunction "GPIO0(USB_HS_ID)_1") (pintype "bidirectional"))
      (node (ref "U11") (pin "B1") (pinfunction "GPIO0(USB_HS_ID)_B1") (pintype "bidirectional"))
      (node (ref "U2") (pin "1") (pinfunction "GPIO0(USB_HS_ID)_1") (pintype "bidirectional"))
      (node (ref "U2") (pin "B1") (pinfunction "GPIO0(USB_HS_ID)_B1") (pintype "bidirectional"))
      (node (ref "U3") (pin "1") (pinfunction "GPIO0(USB_HS_ID)_1") (pintype "bidirectional"))
      (node (ref "U3") (pin "B1") (pinfunction "GPIO0(USB_HS_ID)_B1") (pintype "bidirectional"))
      (node (ref "U4") (pin "1") (pinfunction "GPIO0(USB_HS_ID)_1") (pintype "bidirectional"))
      (node (ref "U4") (pin "B1") (pinfunction "GPIO0(USB_HS_ID)_B1") (pintype "bidirectional"))
      (node (ref "U5") (pin "1") (pinfunction "GPIO0(USB_HS_ID)_1") (pintype "bidirectional"))
      (node (ref "U5") (pin "B1") (pinfunction "GPIO0(USB_HS_ID)_B1") (pintype "bidirectional"))
      (node (ref "U6") (pin "1") (pinfunction "GPIO0(USB_HS_ID)_1") (pintype "bidirectional"))
      (node (ref "U6") (pin "B1") (pinfunction "GPIO0(USB_HS_ID)_B1") (pintype "bidirectional"))
      (node (ref "U7") (pin "1") (pinfunction "GPIO0(USB_HS_ID)_1") (pintype "bidirectional"))
      (node (ref "U7") (pin "B1") (pinfunction "GPIO0(USB_HS_ID)_B1") (pintype "bidirectional"))
      (node (ref "U8") (pin "1") (pinfunction "GPIO0(USB_HS_ID)_1") (pintype "bidirectional"))
      (node (ref "U8") (pin "B1") (pinfunction "GPIO0(USB_HS_ID)_B1") (pintype "bidirectional"))
      (node (ref "U9") (pin "1") (pinfunction "GPIO0(USB_HS_ID)_1") (pintype "bidirectional"))
      (node (ref "U9") (pin "B1") (pinfunction "GPIO0(USB_HS_ID)_B1") (pintype "bidirectional"))
    )
    (net (code "16") (name "MISO_2") (class "Default")
      (node (ref "R27") (pin "1") (pinfunction "1_1") (pintype "passive"))
      (node (ref "U7") (pin "10") (pinfunction "GPIO9(SPI1_MISO)_10") (pintype "bidirectional"))
      (node (ref "U7") (pin "B10") (pinfunction "GPIO9(SPI1_MISO)_B10") (pintype "bidirectional"))
    )
    (net (code "17") (name "MOSI_2") (class "Default")
      (node (ref "U10") (pin "11") (pinfunction "GPIO10(SPI1_MOSI)_11") (pintype "bidirectional"))
      (node (ref "U10") (pin "B11") (pinfunction "GPIO10(SPI1_MOSI)_B11") (pintype "bidirectional"))
      (node (ref "U11") (pin "11") (pinfunction "GPIO10(SPI1_MOSI)_11") (pintype "bidirectional"))
      (node (ref "U11") (pin "B11") (pinfunction "GPIO10(SPI1_MOSI)_B11") (pintype "bidirectional"))
      (node (ref "U2") (pin "11") (pinfunction "GPIO10(SPI1_MOSI)_11") (pintype "bidirectional"))
      (node (ref "U2") (pin "B11") (pinfunction "GPIO10(SPI1_MOSI)_B11") (pintype "bidirectional"))
      (node (ref "U3") (pin "11") (pinfunction "GPIO10(SPI1_MOSI)_11") (pintype "bidirectional"))
      (node (ref "U3") (pin "B11") (pinfunction "GPIO10(SPI1_MOSI)_B11") (pintype "bidirectional"))
      (node (ref "U4") (pin "11") (pinfunction "GPIO10(SPI1_MOSI)_11") (pintype "bidirectional"))
      (node (ref "U4") (pin "B11") (pinfunction "GPIO10(SPI1_MOSI)_B11") (pintype "bidirectional"))
      (node (ref "U5") (pin "11") (pinfunction "GPIO10(SPI1_MOSI)_11") (pintype "bidirectional"))
      (node (ref "U5") (pin "B11") (pinfunction "GPIO10(SPI1_MOSI)_B11") (pintype "bidirectional"))
      (node (ref "U6") (pin "11") (pinfunction "GPIO10(SPI1_MOSI)_11") (pintype "bidirectional"))
      (node (ref "U6") (pin "B11") (pinfunction "GPIO10(SPI1_MOSI)_B11") (pintype "bidirectional"))
      (node (ref "U7") (pin "11") (pinfunction "GPIO10(SPI1_MOSI)_11") (pintype "bidirectional"))
      (node (ref "U7") (pin "B11") (pinfunction "GPIO10(SPI1_MOSI)_B11") (pintype "bidirectional"))
      (node (ref "U8") (pin "11") (pinfunction "GPIO10(SPI1_MOSI)_11") (pintype "bidirectional"))
      (node (ref "U8") (pin "B11") (pinfunction "GPIO10(SPI1_MOSI)_B11") (pintype "bidirectional"))
      (node (ref "U9") (pin "11") (pinfunction "GPIO10(SPI1_MOSI)_11") (pintype "bidirectional"))
      (node (ref "U9") (pin "B11") (pinfunction "GPIO10(SPI1_MOSI)_B11") (pintype "bidirectional"))
      (node (ref "X1") (pin "12") (pinfunction "KL_12") (pintype "passive"))
    )
    (net (code "18") (name "Net-(C16-Pad-)") (class "Default")
      (node (ref "C16") (pin "-") (pinfunction "-_-") (pintype "passive"))
      (node (ref "R3") (pin "1") (pinfunction "1_1") (pintype "passive"))
    )
    (net (code "19") (name "Net-(C21-Pad2)") (class "Default")
      (node (ref "C21") (pin "2") (pinfunction "2_2") (pintype "passive"))
      (node (ref "R6") (pin "1") (pinfunction "1_1") (pintype "passive"))
      (node (ref "R7") (pin "2") (pinfunction "2_2") (pintype "passive"))
      (node (ref "R8") (pin "1") (pinfunction "1_1") (pintype "passive"))
    )
    (net (code "20") (name "Net-(C25-Pad2)") (class "Default")
      (node (ref "C25") (pin "2") (pinfunction "2_2") (pintype "passive"))
      (node (ref "R1") (pin "1") (pinfunction "1_1") (pintype "passive"))
      (node (ref "R23") (pin "1") (pinfunction "1_1") (pintype "passive"))
      (node (ref "R56") (pin "2") (pinfunction "2_2") (pintype "passive"))
    )
    (net (code "21") (name "Net-(C26-Pad2)") (class "Default")
      (node (ref "C26") (pin "2") (pinfunction "2_2") (pintype "passive"))
      (node (ref "R12") (pin "2") (pinfunction "2_2") (pintype "passive"))
      (node (ref "R13") (pin "1") (pinfunction "1_1") (pintype "passive"))
      (node (ref "R9") (pin "1") (pinfunction "1_1") (pintype "passive"))
    )
    (net (code "22") (name "Net-(C27-Pad2)") (class "Default")
      (node (ref "C27") (pin "2") (pinfunction "2_2") (pintype "passive"))
      (node (ref "R14") (pin "1") (pinfunction "1_1") (pintype "passive"))
      (node (ref "R15") (pin "2") (pinfunction "2_2") (pintype "passive"))
      (node (ref "R16") (pin "1") (pinfunction "1_1") (pintype "passive"))
    )
    (net (code "23") (name "Net-(C29-Pad2)") (class "Default")
      (node (ref "C29") (pin "2") (pinfunction "2_2") (pintype "passive"))
      (node (ref "R17") (pin "1") (pinfunction "1_1") (pintype "passive"))
      (node (ref "R18") (pin "2") (pinfunction "2_2") (pintype "passive"))
      (node (ref "R19") (pin "1") (pinfunction "1_1") (pintype "passive"))
    )
    (net (code "24") (name "Net-(C31-Pad2)") (class "Default")
      (node (ref "C31") (pin "2") (pinfunction "2_2") (pintype "passive"))
      (node (ref "R20") (pin "1") (pinfunction "1_1") (pintype "passive"))
      (node (ref "R21") (pin "2") (pinfunction "2_2") (pintype "passive"))
      (node (ref "R22") (pin "1") (pinfunction "1_1") (pintype "passive"))
    )
    (net (code "25") (name "Net-(J1-Pad1)") (class "Default")
      (node (ref "J1") (pin "1") (pinfunction "1_1") (pintype "bidirectional"))
      (node (ref "J1") (pin "2") (pinfunction "2_2") (pintype "bidirectional"))
      (node (ref "JP12") (pin "1") (pinfunction "1_1") (pintype "passive"))
      (node (ref "R3") (pin "2") (pinfunction "2_2") (pintype "passive"))
      (node (ref "R5") (pin "2") (pinfunction "2_2") (pintype "passive"))
    )
    (net (code "26") (name "Net-(PS1-VIN)") (class "Default")
      (node (ref "C22") (pin "1") (pinfunction "1_1") (pintype "passive"))
      (node (ref "L1") (pin "P$2") (pinfunction "P$2_P$2") (pintype "bidirectional"))
      (node (ref "PS1") (pin "2") (pinfunction "VIN_2") (pintype "input"))
    )
    (net (code "27") (name "Net-(S1-S)") (class "Default")
      (node (ref "S1") (pin "1") (pinfunction "S_1") (pintype "passive"))
      (node (ref "S1") (pin "2") (pinfunction "S1_2") (pintype "passive"))
      (node (ref "U7") (pin "14") (pinfunction "GPIO13(USART1_TX)_14") (pintype "bidirectional"))
      (node (ref "U7") (pin "B14") (pinfunction "GPIO13(USART1_TX)_B14") (pintype "bidirectional"))
    )
    (net (code "28") (name "Net-(U1--IN)") (class "Default")
      (node (ref "C20") (pin "1") (pinfunction "1_1") (pintype "passive"))
      (node (ref "R1") (pin "2") (pinfunction "2_2") (pintype "passive"))
      (node (ref "R13") (pin "2") (pinfunction "2_2") (pintype "passive"))
      (node (ref "R16") (pin "2") (pinfunction "2_2") (pintype "passive"))
      (node (ref "R19") (pin "2") (pinfunction "2_2") (pintype "passive"))
      (node (ref "R2") (pin "1") (pinfunction "1_1") (pintype "passive"))
      (node (ref "R22") (pin "2") (pinfunction "2_2") (pintype "passive"))
      (node (ref "R8") (pin "2") (pinfunction "2_2") (pintype "passive"))
      (node (ref "U1") (pin "2") (pinfunction "-IN_2") (pintype "input"))
    )
    (net (code "29") (name "Net-(U1-OUT)") (class "Default")
      (node (ref "C16") (pin "+") (pinfunction "+_+") (pintype "passive"))
      (node (ref "C20") (pin "2") (pinfunction "2_2") (pintype "passive"))
      (node (ref "R2") (pin "2") (pinfunction "2_2") (pintype "passive"))
      (node (ref "U1") (pin "6") (pinfunction "OUT_6") (pintype "output"))
    )
    (net (code "30") (name "Net-(U2-+3V3_A-Pad21)") (class "Default")
      (node (ref "U2") (pin "21") (pinfunction "+3V3_A_21") (pintype "bidirectional"))
      (node (ref "U2") (pin "B21") (pinfunction "+3V3_A_B21") (pintype "bidirectional"))
    )
    (net (code "31") (name "Net-(U2-AUDIO_IN_L-Pad16)") (class "Default")
      (node (ref "U2") (pin "16") (pinfunction "AUDIO_IN_L_16") (pintype "bidirectional"))
      (node (ref "U2") (pin "B16") (pinfunction "AUDIO_IN_L_B16") (pintype "bidirectional"))
    )
    (net (code "32") (name "Net-(U2-AUDIO_IN_R-Pad17)") (class "Default")
      (node (ref "U2") (pin "17") (pinfunction "AUDIO_IN_R_17") (pintype "bidirectional"))
      (node (ref "U2") (pin "B17") (pinfunction "AUDIO_IN_R_B17") (pintype "bidirectional"))
    )
    (net (code "33") (name "Net-(U2-AUDIO_OUT_R-Pad19)") (class "Default")
      (node (ref "U2") (pin "19") (pinfunction "AUDIO_OUT_R_19") (pintype "bidirectional"))
      (node (ref "U2") (pin "B19") (pinfunction "AUDIO_OUT_R_B19") (pintype "bidirectional"))
    )
    (net (code "34") (name "Net-(U2-GPIO1(SDMMC1_D3)-Pad2)") (class "Default")
      (node (ref "U2") (pin "2") (pinfunction "GPIO1(SDMMC1_D3)_2") (pintype "bidirectional"))
      (node (ref "U2") (pin "B2") (pinfunction "GPIO1(SDMMC1_D3)_B2") (pintype "bidirectional"))
    )
    (net (code "35") (name "Net-(U2-GPIO2(SDMMC1_D2)-Pad3)") (class "Default")
      (node (ref "U2") (pin "3") (pinfunction "GPIO2(SDMMC1_D2)_3") (pintype "bidirectional"))
      (node (ref "U2") (pin "B3") (pinfunction "GPIO2(SDMMC1_D2)_B3") (pintype "bidirectional"))
    )
    (net (code "36") (name "Net-(U2-GPIO3(SDMMC1_D1)-Pad4)") (class "Default")
      (node (ref "U2") (pin "4") (pinfunction "GPIO3(SDMMC1_D1)_4") (pintype "bidirectional"))
      (node (ref "U2") (pin "B4") (pinfunction "GPIO3(SDMMC1_D1)_B4") (pintype "bidirectional"))
    )
    (net (code "37") (name "Net-(U2-GPIO4(SDMMC1_D0)-Pad5)") (class "Default")
      (node (ref "U2") (pin "5") (pinfunction "GPIO4(SDMMC1_D0)_5") (pintype "bidirectional"))
      (node (ref "U2") (pin "B5") (pinfunction "GPIO4(SDMMC1_D0)_B5") (pintype "bidirectional"))
    )
    (net (code "38") (name "Net-(U2-GPIO5(SDMMC1_CMD)-Pad6)") (class "Default")
      (node (ref "U2") (pin "6") (pinfunction "GPIO5(SDMMC1_CMD)_6") (pintype "bidirectional"))
      (node (ref "U2") (pin "B6") (pinfunction "GPIO5(SDMMC1_CMD)_B6") (pintype "bidirectional"))
    )
    (net (code "39") (name "Net-(U2-GPIO6(SDMMC1_CK)-Pad7)") (class "Default")
      (node (ref "U2") (pin "7") (pinfunction "GPIO6(SDMMC1_CK)_7") (pintype "bidirectional"))
      (node (ref "U2") (pin "B7") (pinfunction "GPIO6(SDMMC1_CK)_B7") (pintype "bidirectional"))
    )
    (net (code "40") (name "Net-(U2-GPIO9(SPI1_MISO)-Pad10)") (class "Default")
      (node (ref "U2") (pin "10") (pinfunction "GPIO9(SPI1_MISO)_10") (pintype "bidirectional"))
      (node (ref "U2") (pin "B10") (pinfunction "GPIO9(SPI1_MISO)_B10") (pintype "bidirectional"))
    )
    (net (code "41") (name "Net-(U2-GPIO13(USART1_TX)-Pad14)") (class "Default")
      (node (ref "U2") (pin "14") (pinfunction "GPIO13(USART1_TX)_14") (pintype "bidirectional"))
      (node (ref "U2") (pin "B14") (pinfunction "GPIO13(USART1_TX)_B14") (pintype "bidirectional"))
    )
    (net (code "42") (name "Net-(U2-GPIO14(USART1_RX)-Pad15)") (class "Default")
      (node (ref "U2") (pin "15") (pinfunction "GPIO14(USART1_RX)_15") (pintype "bidirectional"))
      (node (ref "U2") (pin "B15") (pinfunction "GPIO14(USART1_RX)_B15") (pintype "bidirectional"))
    )
    (net (code "43") (name "Net-(U2-GPIO15(ADC0)-Pad22)") (class "Default")
      (node (ref "U2") (pin "22") (pinfunction "GPIO15(ADC0)_22") (pintype "bidirectional"))
      (node (ref "U2") (pin "B22") (pinfunction "GPIO15(ADC0)_B22") (pintype "bidirectional"))
    )
    (net (code "44") (name "Net-(U2-GPIO16(ADC1)-Pad23)") (class "Default")
      (node (ref "U2") (pin "23") (pinfunction "GPIO16(ADC1)_23") (pintype "bidirectional"))
      (node (ref "U2") (pin "B23") (pinfunction "GPIO16(ADC1)_B23") (pintype "bidirectional"))
    )
    (net (code "45") (name "Net-(U2-GPIO17(ADC2)-Pad24)") (class "Default")
      (node (ref "U2") (pin "24") (pinfunction "GPIO17(ADC2)_24") (pintype "bidirectional"))
      (node (ref "U2") (pin "B24") (pinfunction "GPIO17(ADC2)_B24") (pintype "bidirectional"))
    )
    (net (code "46") (name "Net-(U2-GPIO19(ADC4)-Pad26)") (class "Default")
      (node (ref "U2") (pin "26") (pinfunction "GPIO19(ADC4)_26") (pintype "bidirectional"))
      (node (ref "U2") (pin "B26") (pinfunction "GPIO19(ADC4)_B26") (pintype "bidirectional"))
    )
    (net (code "47") (name "Net-(U2-GPIO20(ADC5)-Pad27)") (class "Default")
      (node (ref "U2") (pin "27") (pinfunction "GPIO20(ADC5)_27") (pintype "bidirectional"))
      (node (ref "U2") (pin "B27") (pinfunction "GPIO20(ADC5)_B27") (pintype "bidirectional"))
    )
    (net (code "48") (name "Net-(U2-GPIO21(ADC6)-Pad28)") (class "Default")
      (node (ref "U2") (pin "28") (pinfunction "GPIO21(ADC6)_28") (pintype "bidirectional"))
      (node (ref "U2") (pin "B28") (pinfunction "GPIO21(ADC6)_B28") (pintype "bidirectional"))
    )
    (net (code "49") (name "Net-(U2-GPIO24(ADC9)-Pad31)") (class "Default")
      (node (ref "U2") (pin "31") (pinfunction "GPIO24(ADC9)_31") (pintype "bidirectional"))
      (node (ref "U2") (pin "B31") (pinfunction "GPIO24(ADC9)_B31") (pintype "bidirectional"))
    )
    (net (code "50") (name "Net-(U2-GPIO25(ADC10)-Pad32)") (class "Default")
      (node (ref "U2") (pin "32") (pinfunction "GPIO25(ADC10)_32") (pintype "bidirectional"))
      (node (ref "U2") (pin "B32") (pinfunction "GPIO25(ADC10)_B32") (pintype "bidirectional"))
    )
    (net (code "51") (name "Net-(U2-GPIO26(SAI2_SD_A)-Pad33)") (class "Default")
      (node (ref "U2") (pin "33") (pinfunction "GPIO26(SAI2_SD_A)_33") (pintype "bidirectional"))
      (node (ref "U2") (pin "B33") (pinfunction "GPIO26(SAI2_SD_A)_B33") (pintype "bidirectional"))
    )
    (net (code "52") (name "Net-(U2-GPIO27(SAI2_FS_B)-Pad34)") (class "Default")
      (node (ref "U2") (pin "34") (pinfunction "GPIO27(SAI2_FS_B)_34") (pintype "bidirectional"))
      (node (ref "U2") (pin "B34") (pinfunction "GPIO27(SAI2_FS_B)_B34") (pintype "bidirectional"))
    )
    (net (code "53") (name "Net-(U3-+3V3_A-Pad21)") (class "Default")
      (node (ref "U3") (pin "21") (pinfunction "+3V3_A_21") (pintype "bidirectional"))
      (node (ref "U3") (pin "B21") (pinfunction "+3V3_A_B21") (pintype "bidirectional"))
    )
    (net (code "54") (name "Net-(U3-+3V3_D-Pad38)") (class "Default")
      (node (ref "U3") (pin "35") (pinfunction "GPIO28(ADC11)_35") (pintype "bidirectional"))
      (node (ref "U3") (pin "38") (pinfunction "+3V3_D_38") (pintype "bidirectional"))
      (node (ref "U3") (pin "B35") (pinfunction "GPIO28(ADC11)_B35") (pintype "bidirectional"))
      (node (ref "U3") (pin "B38") (pinfunction "+3V3_D_B38") (pintype "bidirectional"))
    )
    (net (code "55") (name "Net-(U3-AUDIO_IN_L-Pad16)") (class "Default")
      (node (ref "U3") (pin "16") (pinfunction "AUDIO_IN_L_16") (pintype "bidirectional"))
      (node (ref "U3") (pin "B16") (pinfunction "AUDIO_IN_L_B16") (pintype "bidirectional"))
    )
    (net (code "56") (name "Net-(U3-AUDIO_IN_R-Pad17)") (class "Default")
      (node (ref "U3") (pin "17") (pinfunction "AUDIO_IN_R_17") (pintype "bidirectional"))
      (node (ref "U3") (pin "B17") (pinfunction "AUDIO_IN_R_B17") (pintype "bidirectional"))
    )
    (net (code "57") (name "Net-(U3-AUDIO_OUT_R-Pad19)") (class "Default")
      (node (ref "U3") (pin "19") (pinfunction "AUDIO_OUT_R_19") (pintype "bidirectional"))
      (node (ref "U3") (pin "B19") (pinfunction "AUDIO_OUT_R_B19") (pintype "bidirectional"))
    )
    (net (code "58") (name "Net-(U3-GPIO1(SDMMC1_D3)-Pad2)") (class "Default")
      (node (ref "U3") (pin "2") (pinfunction "GPIO1(SDMMC1_D3)_2") (pintype "bidirectional"))
      (node (ref "U3") (pin "B2") (pinfunction "GPIO1(SDMMC1_D3)_B2") (pintype "bidirectional"))
    )
    (net (code "59") (name "Net-(U3-GPIO2(SDMMC1_D2)-Pad3)") (class "Default")
      (node (ref "U3") (pin "3") (pinfunction "GPIO2(SDMMC1_D2)_3") (pintype "bidirectional"))
      (node (ref "U3") (pin "B3") (pinfunction "GPIO2(SDMMC1_D2)_B3") (pintype "bidirectional"))
    )
    (net (code "60") (name "Net-(U3-GPIO3(SDMMC1_D1)-Pad4)") (class "Default")
      (node (ref "U3") (pin "4") (pinfunction "GPIO3(SDMMC1_D1)_4") (pintype "bidirectional"))
      (node (ref "U3") (pin "B4") (pinfunction "GPIO3(SDMMC1_D1)_B4") (pintype "bidirectional"))
    )
    (net (code "61") (name "Net-(U3-GPIO4(SDMMC1_D0)-Pad5)") (class "Default")
      (node (ref "U3") (pin "5") (pinfunction "GPIO4(SDMMC1_D0)_5") (pintype "bidirectional"))
      (node (ref "U3") (pin "B5") (pinfunction "GPIO4(SDMMC1_D0)_B5") (pintype "bidirectional"))
    )
    (net (code "62") (name "Net-(U3-GPIO5(SDMMC1_CMD)-Pad6)") (class "Default")
      (node (ref "U3") (pin "6") (pinfunction "GPIO5(SDMMC1_CMD)_6") (pintype "bidirectional"))
      (node (ref "U3") (pin "B6") (pinfunction "GPIO5(SDMMC1_CMD)_B6") (pintype "bidirectional"))
    )
    (net (code "63") (name "Net-(U3-GPIO6(SDMMC1_CK)-Pad7)") (class "Default")
      (node (ref "U3") (pin "7") (pinfunction "GPIO6(SDMMC1_CK)_7") (pintype "bidirectional"))
      (node (ref "U3") (pin "B7") (pinfunction "GPIO6(SDMMC1_CK)_B7") (pintype "bidirectional"))
    )
    (net (code "64") (name "Net-(U3-GPIO9(SPI1_MISO)-Pad10)") (class "Default")
      (node (ref "U3") (pin "10") (pinfunction "GPIO9(SPI1_MISO)_10") (pintype "bidirectional"))
      (node (ref "U3") (pin "B10") (pinfunction "GPIO9(SPI1_MISO)_B10") (pintype "bidirectional"))
    )
    (net (code "65") (name "Net-(U3-GPIO13(USART1_TX)-Pad14)") (class "Default")
      (node (ref "U3") (pin "14") (pinfunction "GPIO13(USART1_TX)_14") (pintype "bidirectional"))
      (node (ref "U3") (pin "B14") (pinfunction "GPIO13(USART1_TX)_B14") (pintype "bidirectional"))
    )
    (net (code "66") (name "Net-(U3-GPIO14(USART1_RX)-Pad15)") (class "Default")
      (node (ref "U3") (pin "15") (pinfunction "GPIO14(USART1_RX)_15") (pintype "bidirectional"))
      (node (ref "U3") (pin "B15") (pinfunction "GPIO14(USART1_RX)_B15") (pintype "bidirectional"))
    )
    (net (code "67") (name "Net-(U3-GPIO15(ADC0)-Pad22)") (class "Default")
      (node (ref "U3") (pin "22") (pinfunction "GPIO15(ADC0)_22") (pintype "bidirectional"))
      (node (ref "U3") (pin "B22") (pinfunction "GPIO15(ADC0)_B22") (pintype "bidirectional"))
    )
    (net (code "68") (name "Net-(U3-GPIO16(ADC1)-Pad23)") (class "Default")
      (node (ref "U3") (pin "23") (pinfunction "GPIO16(ADC1)_23") (pintype "bidirectional"))
      (node (ref "U3") (pin "B23") (pinfunction "GPIO16(ADC1)_B23") (pintype "bidirectional"))
    )
    (net (code "69") (name "Net-(U3-GPIO17(ADC2)-Pad24)") (class "Default")
      (node (ref "U3") (pin "24") (pinfunction "GPIO17(ADC2)_24") (pintype "bidirectional"))
      (node (ref "U3") (pin "B24") (pinfunction "GPIO17(ADC2)_B24") (pintype "bidirectional"))
    )
    (net (code "70") (name "Net-(U3-GPIO19(ADC4)-Pad26)") (class "Default")
      (node (ref "U3") (pin "26") (pinfunction "GPIO19(ADC4)_26") (pintype "bidirectional"))
      (node (ref "U3") (pin "B26") (pinfunction "GPIO19(ADC4)_B26") (pintype "bidirectional"))
    )
    (net (code "71") (name "Net-(U3-GPIO20(ADC5)-Pad27)") (class "Default")
      (node (ref "U3") (pin "27") (pinfunction "GPIO20(ADC5)_27") (pintype "bidirectional"))
      (node (ref "U3") (pin "B27") (pinfunction "GPIO20(ADC5)_B27") (pintype "bidirectional"))
    )
    (net (code "72") (name "Net-(U3-GPIO21(ADC6)-Pad28)") (class "Default")
      (node (ref "U3") (pin "28") (pinfunction "GPIO21(ADC6)_28") (pintype "bidirectional"))
      (node (ref "U3") (pin "B28") (pinfunction "GPIO21(ADC6)_B28") (pintype "bidirectional"))
    )
    (net (code "73") (name "Net-(U3-GPIO25(ADC10)-Pad32)") (class "Default")
      (node (ref "U3") (pin "32") (pinfunction "GPIO25(ADC10)_32") (pintype "bidirectional"))
      (node (ref "U3") (pin "B32") (pinfunction "GPIO25(ADC10)_B32") (pintype "bidirectional"))
    )
    (net (code "74") (name "Net-(U3-GPIO26(SAI2_SD_A)-Pad33)") (class "Default")
      (node (ref "U3") (pin "33") (pinfunction "GPIO26(SAI2_SD_A)_33") (pintype "bidirectional"))
      (node (ref "U3") (pin "B33") (pinfunction "GPIO26(SAI2_SD_A)_B33") (pintype "bidirectional"))
    )
    (net (code "75") (name "Net-(U3-GPIO27(SAI2_FS_B)-Pad34)") (class "Default")
      (node (ref "U3") (pin "34") (pinfunction "GPIO27(SAI2_FS_B)_34") (pintype "bidirectional"))
      (node (ref "U3") (pin "B34") (pinfunction "GPIO27(SAI2_FS_B)_B34") (pintype "bidirectional"))
    )
    (net (code "76") (name "Net-(U4-+3V3_A-Pad21)") (class "Default")
      (node (ref "U4") (pin "21") (pinfunction "+3V3_A_21") (pintype "bidirectional"))
      (node (ref "U4") (pin "B21") (pinfunction "+3V3_A_B21") (pintype "bidirectional"))
    )
    (net (code "77") (name "Net-(U4-AUDIO_IN_L-Pad16)") (class "Default")
      (node (ref "U4") (pin "16") (pinfunction "AUDIO_IN_L_16") (pintype "bidirectional"))
      (node (ref "U4") (pin "B16") (pinfunction "AUDIO_IN_L_B16") (pintype "bidirectional"))
    )
    (net (code "78") (name "Net-(U4-AUDIO_IN_R-Pad17)") (class "Default")
      (node (ref "U4") (pin "17") (pinfunction "AUDIO_IN_R_17") (pintype "bidirectional"))
      (node (ref "U4") (pin "B17") (pinfunction "AUDIO_IN_R_B17") (pintype "bidirectional"))
    )
    (net (code "79") (name "Net-(U4-AUDIO_OUT_R-Pad19)") (class "Default")
      (node (ref "U4") (pin "19") (pinfunction "AUDIO_OUT_R_19") (pintype "bidirectional"))
      (node (ref "U4") (pin "B19") (pinfunction "AUDIO_OUT_R_B19") (pintype "bidirectional"))
    )
    (net (code "80") (name "Net-(U4-GPIO1(SDMMC1_D3)-Pad2)") (class "Default")
      (node (ref "U4") (pin "2") (pinfunction "GPIO1(SDMMC1_D3)_2") (pintype "bidirectional"))
      (node (ref "U4") (pin "B2") (pinfunction "GPIO1(SDMMC1_D3)_B2") (pintype "bidirectional"))
    )
    (net (code "81") (name "Net-(U4-GPIO2(SDMMC1_D2)-Pad3)") (class "Default")
      (node (ref "U4") (pin "3") (pinfunction "GPIO2(SDMMC1_D2)_3") (pintype "bidirectional"))
      (node (ref "U4") (pin "B3") (pinfunction "GPIO2(SDMMC1_D2)_B3") (pintype "bidirectional"))
    )
    (net (code "82") (name "Net-(U4-GPIO3(SDMMC1_D1)-Pad4)") (class "Default")
      (node (ref "U4") (pin "4") (pinfunction "GPIO3(SDMMC1_D1)_4") (pintype "bidirectional"))
      (node (ref "U4") (pin "B4") (pinfunction "GPIO3(SDMMC1_D1)_B4") (pintype "bidirectional"))
    )
    (net (code "83") (name "Net-(U4-GPIO4(SDMMC1_D0)-Pad5)") (class "Default")
      (node (ref "U4") (pin "5") (pinfunction "GPIO4(SDMMC1_D0)_5") (pintype "bidirectional"))
      (node (ref "U4") (pin "B5") (pinfunction "GPIO4(SDMMC1_D0)_B5") (pintype "bidirectional"))
    )
    (net (code "84") (name "Net-(U4-GPIO5(SDMMC1_CMD)-Pad6)") (class "Default")
      (node (ref "U4") (pin "6") (pinfunction "GPIO5(SDMMC1_CMD)_6") (pintype "bidirectional"))
      (node (ref "U4") (pin "B6") (pinfunction "GPIO5(SDMMC1_CMD)_B6") (pintype "bidirectional"))
    )
    (net (code "85") (name "Net-(U4-GPIO6(SDMMC1_CK)-Pad7)") (class "Default")
      (node (ref "U4") (pin "7") (pinfunction "GPIO6(SDMMC1_CK)_7") (pintype "bidirectional"))
      (node (ref "U4") (pin "B7") (pinfunction "GPIO6(SDMMC1_CK)_B7") (pintype "bidirectional"))
    )
    (net (code "86") (name "Net-(U4-GPIO9(SPI1_MISO)-Pad10)") (class "Default")
      (node (ref "U4") (pin "10") (pinfunction "GPIO9(SPI1_MISO)_10") (pintype "bidirectional"))
      (node (ref "U4") (pin "B10") (pinfunction "GPIO9(SPI1_MISO)_B10") (pintype "bidirectional"))
    )
    (net (code "87") (name "Net-(U4-GPIO13(USART1_TX)-Pad14)") (class "Default")
      (node (ref "U4") (pin "14") (pinfunction "GPIO13(USART1_TX)_14") (pintype "bidirectional"))
      (node (ref "U4") (pin "B14") (pinfunction "GPIO13(USART1_TX)_B14") (pintype "bidirectional"))
    )
    (net (code "88") (name "Net-(U4-GPIO14(USART1_RX)-Pad15)") (class "Default")
      (node (ref "U4") (pin "15") (pinfunction "GPIO14(USART1_RX)_15") (pintype "bidirectional"))
      (node (ref "U4") (pin "B15") (pinfunction "GPIO14(USART1_RX)_B15") (pintype "bidirectional"))
    )
    (net (code "89") (name "Net-(U4-GPIO15(ADC0)-Pad22)") (class "Default")
      (node (ref "U4") (pin "22") (pinfunction "GPIO15(ADC0)_22") (pintype "bidirectional"))
      (node (ref "U4") (pin "B22") (pinfunction "GPIO15(ADC0)_B22") (pintype "bidirectional"))
    )
    (net (code "90") (name "Net-(U4-GPIO16(ADC1)-Pad23)") (class "Default")
      (node (ref "U4") (pin "23") (pinfunction "GPIO16(ADC1)_23") (pintype "bidirectional"))
      (node (ref "U4") (pin "B23") (pinfunction "GPIO16(ADC1)_B23") (pintype "bidirectional"))
    )
    (net (code "91") (name "Net-(U4-GPIO17(ADC2)-Pad24)") (class "Default")
      (node (ref "U4") (pin "24") (pinfunction "GPIO17(ADC2)_24") (pintype "bidirectional"))
      (node (ref "U4") (pin "B24") (pinfunction "GPIO17(ADC2)_B24") (pintype "bidirectional"))
    )
    (net (code "92") (name "Net-(U4-GPIO19(ADC4)-Pad26)") (class "Default")
      (node (ref "U4") (pin "26") (pinfunction "GPIO19(ADC4)_26") (pintype "bidirectional"))
      (node (ref "U4") (pin "B26") (pinfunction "GPIO19(ADC4)_B26") (pintype "bidirectional"))
    )
    (net (code "93") (name "Net-(U4-GPIO20(ADC5)-Pad27)") (class "Default")
      (node (ref "U4") (pin "27") (pinfunction "GPIO20(ADC5)_27") (pintype "bidirectional"))
      (node (ref "U4") (pin "B27") (pinfunction "GPIO20(ADC5)_B27") (pintype "bidirectional"))
    )
    (net (code "94") (name "Net-(U4-GPIO21(ADC6)-Pad28)") (class "Default")
      (node (ref "U4") (pin "28") (pinfunction "GPIO21(ADC6)_28") (pintype "bidirectional"))
      (node (ref "U4") (pin "B28") (pinfunction "GPIO21(ADC6)_B28") (pintype "bidirectional"))
    )
    (net (code "95") (name "Net-(U4-GPIO24(ADC9)-Pad31)") (class "Default")
      (node (ref "U4") (pin "31") (pinfunction "GPIO24(ADC9)_31") (pintype "bidirectional"))
      (node (ref "U4") (pin "B31") (pinfunction "GPIO24(ADC9)_B31") (pintype "bidirectional"))
    )
    (net (code "96") (name "Net-(U4-GPIO25(ADC10)-Pad32)") (class "Default")
      (node (ref "U4") (pin "32") (pinfunction "GPIO25(ADC10)_32") (pintype "bidirectional"))
      (node (ref "U4") (pin "B32") (pinfunction "GPIO25(ADC10)_B32") (pintype "bidirectional"))
    )
    (net (code "97") (name "Net-(U4-GPIO26(SAI2_SD_A)-Pad33)") (class "Default")
      (node (ref "U4") (pin "33") (pinfunction "GPIO26(SAI2_SD_A)_33") (pintype "bidirectional"))
      (node (ref "U4") (pin "B33") (pinfunction "GPIO26(SAI2_SD_A)_B33") (pintype "bidirectional"))
    )
    (net (code "98") (name "Net-(U4-GPIO27(SAI2_FS_B)-Pad34)") (class "Default")
      (node (ref "U4") (pin "34") (pinfunction "GPIO27(SAI2_FS_B)_34") (pintype "bidirectional"))
      (node (ref "U4") (pin "B34") (pinfunction "GPIO27(SAI2_FS_B)_B34") (pintype "bidirectional"))
    )
    (net (code "99") (name "Net-(U5-+3V3_A-Pad21)") (class "Default")
      (node (ref "U5") (pin "21") (pinfunction "+3V3_A_21") (pintype "bidirectional"))
      (node (ref "U5") (pin "B21") (pinfunction "+3V3_A_B21") (pintype "bidirectional"))
    )
    (net (code "100") (name "Net-(U5-AUDIO_IN_L-Pad16)") (class "Default")
      (node (ref "U5") (pin "16") (pinfunction "AUDIO_IN_L_16") (pintype "bidirectional"))
      (node (ref "U5") (pin "B16") (pinfunction "AUDIO_IN_L_B16") (pintype "bidirectional"))
    )
    (net (code "101") (name "Net-(U5-AUDIO_IN_R-Pad17)") (class "Default")
      (node (ref "U5") (pin "17") (pinfunction "AUDIO_IN_R_17") (pintype "bidirectional"))
      (node (ref "U5") (pin "B17") (pinfunction "AUDIO_IN_R_B17") (pintype "bidirectional"))
    )
    (net (code "102") (name "Net-(U5-AUDIO_OUT_R-Pad19)") (class "Default")
      (node (ref "U5") (pin "19") (pinfunction "AUDIO_OUT_R_19") (pintype "bidirectional"))
      (node (ref "U5") (pin "B19") (pinfunction "AUDIO_OUT_R_B19") (pintype "bidirectional"))
    )
    (net (code "103") (name "Net-(U5-GPIO1(SDMMC1_D3)-Pad2)") (class "Default")
      (node (ref "U5") (pin "2") (pinfunction "GPIO1(SDMMC1_D3)_2") (pintype "bidirectional"))
      (node (ref "U5") (pin "B2") (pinfunction "GPIO1(SDMMC1_D3)_B2") (pintype "bidirectional"))
    )
    (net (code "104") (name "Net-(U5-GPIO2(SDMMC1_D2)-Pad3)") (class "Default")
      (node (ref "U5") (pin "3") (pinfunction "GPIO2(SDMMC1_D2)_3") (pintype "bidirectional"))
      (node (ref "U5") (pin "B3") (pinfunction "GPIO2(SDMMC1_D2)_B3") (pintype "bidirectional"))
    )
    (net (code "105") (name "Net-(U5-GPIO3(SDMMC1_D1)-Pad4)") (class "Default")
      (node (ref "U5") (pin "4") (pinfunction "GPIO3(SDMMC1_D1)_4") (pintype "bidirectional"))
      (node (ref "U5") (pin "B4") (pinfunction "GPIO3(SDMMC1_D1)_B4") (pintype "bidirectional"))
    )
    (net (code "106") (name "Net-(U5-GPIO4(SDMMC1_D0)-Pad5)") (class "Default")
      (node (ref "U5") (pin "5") (pinfunction "GPIO4(SDMMC1_D0)_5") (pintype "bidirectional"))
      (node (ref "U5") (pin "B5") (pinfunction "GPIO4(SDMMC1_D0)_B5") (pintype "bidirectional"))
    )
    (net (code "107") (name "Net-(U5-GPIO5(SDMMC1_CMD)-Pad6)") (class "Default")
      (node (ref "U5") (pin "6") (pinfunction "GPIO5(SDMMC1_CMD)_6") (pintype "bidirectional"))
      (node (ref "U5") (pin "B6") (pinfunction "GPIO5(SDMMC1_CMD)_B6") (pintype "bidirectional"))
    )
    (net (code "108") (name "Net-(U5-GPIO6(SDMMC1_CK)-Pad7)") (class "Default")
      (node (ref "U5") (pin "7") (pinfunction "GPIO6(SDMMC1_CK)_7") (pintype "bidirectional"))
      (node (ref "U5") (pin "B7") (pinfunction "GPIO6(SDMMC1_CK)_B7") (pintype "bidirectional"))
    )
    (net (code "109") (name "Net-(U5-GPIO9(SPI1_MISO)-Pad10)") (class "Default")
      (node (ref "U5") (pin "10") (pinfunction "GPIO9(SPI1_MISO)_10") (pintype "bidirectional"))
      (node (ref "U5") (pin "B10") (pinfunction "GPIO9(SPI1_MISO)_B10") (pintype "bidirectional"))
    )
    (net (code "110") (name "Net-(U5-GPIO13(USART1_TX)-Pad14)") (class "Default")
      (node (ref "U5") (pin "14") (pinfunction "GPIO13(USART1_TX)_14") (pintype "bidirectional"))
      (node (ref "U5") (pin "B14") (pinfunction "GPIO13(USART1_TX)_B14") (pintype "bidirectional"))
    )
    (net (code "111") (name "Net-(U5-GPIO14(USART1_RX)-Pad15)") (class "Default")
      (node (ref "U5") (pin "15") (pinfunction "GPIO14(USART1_RX)_15") (pintype "bidirectional"))
      (node (ref "U5") (pin "B15") (pinfunction "GPIO14(USART1_RX)_B15") (pintype "bidirectional"))
    )
    (net (code "112") (name "Net-(U5-GPIO15(ADC0)-Pad22)") (class "Default")
      (node (ref "U5") (pin "22") (pinfunction "GPIO15(ADC0)_22") (pintype "bidirectional"))
      (node (ref "U5") (pin "B22") (pinfunction "GPIO15(ADC0)_B22") (pintype "bidirectional"))
    )
    (net (code "113") (name "Net-(U5-GPIO16(ADC1)-Pad23)") (class "Default")
      (node (ref "U5") (pin "23") (pinfunction "GPIO16(ADC1)_23") (pintype "bidirectional"))
      (node (ref "U5") (pin "B23") (pinfunction "GPIO16(ADC1)_B23") (pintype "bidirectional"))
    )
    (net (code "114") (name "Net-(U5-GPIO17(ADC2)-Pad24)") (class "Default")
      (node (ref "U5") (pin "24") (pinfunction "GPIO17(ADC2)_24") (pintype "bidirectional"))
      (node (ref "U5") (pin "B24") (pinfunction "GPIO17(ADC2)_B24") (pintype "bidirectional"))
    )
    (net (code "115") (name "Net-(U5-GPIO19(ADC4)-Pad26)") (class "Default")
      (node (ref "U5") (pin "26") (pinfunction "GPIO19(ADC4)_26") (pintype "bidirectional"))
      (node (ref "U5") (pin "B26") (pinfunction "GPIO19(ADC4)_B26") (pintype "bidirectional"))
    )
    (net (code "116") (name "Net-(U5-GPIO20(ADC5)-Pad27)") (class "Default")
      (node (ref "U5") (pin "27") (pinfunction "GPIO20(ADC5)_27") (pintype "bidirectional"))
      (node (ref "U5") (pin "B27") (pinfunction "GPIO20(ADC5)_B27") (pintype "bidirectional"))
    )
    (net (code "117") (name "Net-(U5-GPIO21(ADC6)-Pad28)") (class "Default")
      (node (ref "U5") (pin "28") (pinfunction "GPIO21(ADC6)_28") (pintype "bidirectional"))
      (node (ref "U5") (pin "B28") (pinfunction "GPIO21(ADC6)_B28") (pintype "bidirectional"))
    )
    (net (code "118") (name "Net-(U5-GPIO24(ADC9)-Pad31)") (class "Default")
      (node (ref "U5") (pin "31") (pinfunction "GPIO24(ADC9)_31") (pintype "bidirectional"))
      (node (ref "U5") (pin "B31") (pinfunction "GPIO24(ADC9)_B31") (pintype "bidirectional"))
    )
    (net (code "119") (name "Net-(U5-GPIO25(ADC10)-Pad32)") (class "Default")
      (node (ref "U5") (pin "32") (pinfunction "GPIO25(ADC10)_32") (pintype "bidirectional"))
      (node (ref "U5") (pin "B32") (pinfunction "GPIO25(ADC10)_B32") (pintype "bidirectional"))
    )
    (net (code "120") (name "Net-(U5-GPIO26(SAI2_SD_A)-Pad33)") (class "Default")
      (node (ref "U5") (pin "33") (pinfunction "GPIO26(SAI2_SD_A)_33") (pintype "bidirectional"))
      (node (ref "U5") (pin "B33") (pinfunction "GPIO26(SAI2_SD_A)_B33") (pintype "bidirectional"))
    )
    (net (code "121") (name "Net-(U5-GPIO27(SAI2_FS_B)-Pad34)") (class "Default")
      (node (ref "U5") (pin "34") (pinfunction "GPIO27(SAI2_FS_B)_34") (pintype "bidirectional"))
      (node (ref "U5") (pin "B34") (pinfunction "GPIO27(SAI2_FS_B)_B34") (pintype "bidirectional"))
    )
    (net (code "122") (name "Net-(U6-+3V3_A-Pad21)") (class "Default")
      (node (ref "U6") (pin "21") (pinfunction "+3V3_A_21") (pintype "bidirectional"))
      (node (ref "U6") (pin "B21") (pinfunction "+3V3_A_B21") (pintype "bidirectional"))
    )
    (net (code "123") (name "Net-(U6-+3V3_D-Pad38)") (class "Default")
      (node (ref "U6") (pin "37") (pinfunction "GPIO30(USB_HS_D+)_37") (pintype "bidirectional"))
      (node (ref "U6") (pin "38") (pinfunction "+3V3_D_38") (pintype "bidirectional"))
      (node (ref "U6") (pin "B37") (pinfunction "GPIO30(USB_HS_D+)_B37") (pintype "bidirectional"))
      (node (ref "U6") (pin "B38") (pinfunction "+3V3_D_B38") (pintype "bidirectional"))
    )
    (net (code "124") (name "Net-(U6-AUDIO_IN_L-Pad16)") (class "Default")
      (node (ref "U6") (pin "16") (pinfunction "AUDIO_IN_L_16") (pintype "bidirectional"))
      (node (ref "U6") (pin "B16") (pinfunction "AUDIO_IN_L_B16") (pintype "bidirectional"))
    )
    (net (code "125") (name "Net-(U6-AUDIO_IN_R-Pad17)") (class "Default")
      (node (ref "U6") (pin "17") (pinfunction "AUDIO_IN_R_17") (pintype "bidirectional"))
      (node (ref "U6") (pin "B17") (pinfunction "AUDIO_IN_R_B17") (pintype "bidirectional"))
    )
    (net (code "126") (name "Net-(U6-AUDIO_OUT_R-Pad19)") (class "Default")
      (node (ref "U6") (pin "19") (pinfunction "AUDIO_OUT_R_19") (pintype "bidirectional"))
      (node (ref "U6") (pin "B19") (pinfunction "AUDIO_OUT_R_B19") (pintype "bidirectional"))
    )
    (net (code "127") (name "Net-(U6-GPIO1(SDMMC1_D3)-Pad2)") (class "Default")
      (node (ref "U6") (pin "2") (pinfunction "GPIO1(SDMMC1_D3)_2") (pintype "bidirectional"))
      (node (ref "U6") (pin "B2") (pinfunction "GPIO1(SDMMC1_D3)_B2") (pintype "bidirectional"))
    )
    (net (code "128") (name "Net-(U6-GPIO2(SDMMC1_D2)-Pad3)") (class "Default")
      (node (ref "U6") (pin "3") (pinfunction "GPIO2(SDMMC1_D2)_3") (pintype "bidirectional"))
      (node (ref "U6") (pin "B3") (pinfunction "GPIO2(SDMMC1_D2)_B3") (pintype "bidirectional"))
    )
    (net (code "129") (name "Net-(U6-GPIO3(SDMMC1_D1)-Pad4)") (class "Default")
      (node (ref "U6") (pin "4") (pinfunction "GPIO3(SDMMC1_D1)_4") (pintype "bidirectional"))
      (node (ref "U6") (pin "B4") (pinfunction "GPIO3(SDMMC1_D1)_B4") (pintype "bidirectional"))
    )
    (net (code "130") (name "Net-(U6-GPIO4(SDMMC1_D0)-Pad5)") (class "Default")
      (node (ref "U6") (pin "5") (pinfunction "GPIO4(SDMMC1_D0)_5") (pintype "bidirectional"))
      (node (ref "U6") (pin "B5") (pinfunction "GPIO4(SDMMC1_D0)_B5") (pintype "bidirectional"))
    )
    (net (code "131") (name "Net-(U6-GPIO5(SDMMC1_CMD)-Pad6)") (class "Default")
      (node (ref "U6") (pin "6") (pinfunction "GPIO5(SDMMC1_CMD)_6") (pintype "bidirectional"))
      (node (ref "U6") (pin "B6") (pinfunction "GPIO5(SDMMC1_CMD)_B6") (pintype "bidirectional"))
    )
    (net (code "132") (name "Net-(U6-GPIO6(SDMMC1_CK)-Pad7)") (class "Default")
      (node (ref "U6") (pin "7") (pinfunction "GPIO6(SDMMC1_CK)_7") (pintype "bidirectional"))
      (node (ref "U6") (pin "B7") (pinfunction "GPIO6(SDMMC1_CK)_B7") (pintype "bidirectional"))
    )
    (net (code "133") (name "Net-(U6-GPIO9(SPI1_MISO)-Pad10)") (class "Default")
      (node (ref "U6") (pin "10") (pinfunction "GPIO9(SPI1_MISO)_10") (pintype "bidirectional"))
      (node (ref "U6") (pin "B10") (pinfunction "GPIO9(SPI1_MISO)_B10") (pintype "bidirectional"))
    )
    (net (code "134") (name "Net-(U6-GPIO13(USART1_TX)-Pad14)") (class "Default")
      (node (ref "U6") (pin "14") (pinfunction "GPIO13(USART1_TX)_14") (pintype "bidirectional"))
      (node (ref "U6") (pin "B14") (pinfunction "GPIO13(USART1_TX)_B14") (pintype "bidirectional"))
    )
    (net (code "135") (name "Net-(U6-GPIO14(USART1_RX)-Pad15)") (class "Default")
      (node (ref "U6") (pin "15") (pinfunction "GPIO14(USART1_RX)_15") (pintype "bidirectional"))
      (node (ref "U6") (pin "B15") (pinfunction "GPIO14(USART1_RX)_B15") (pintype "bidirectional"))
    )
    (net (code "136") (name "Net-(U6-GPIO15(ADC0)-Pad22)") (class "Default")
      (node (ref "U6") (pin "22") (pinfunction "GPIO15(ADC0)_22") (pintype "bidirectional"))
      (node (ref "U6") (pin "B22") (pinfunction "GPIO15(ADC0)_B22") (pintype "bidirectional"))
    )
    (net (code "137") (name "Net-(U6-GPIO16(ADC1)-Pad23)") (class "Default")
      (node (ref "U6") (pin "23") (pinfunction "GPIO16(ADC1)_23") (pintype "bidirectional"))
      (node (ref "U6") (pin "B23") (pinfunction "GPIO16(ADC1)_B23") (pintype "bidirectional"))
    )
    (net (code "138") (name "Net-(U6-GPIO17(ADC2)-Pad24)") (class "Default")
      (node (ref "U6") (pin "24") (pinfunction "GPIO17(ADC2)_24") (pintype "bidirectional"))
      (node (ref "U6") (pin "B24") (pinfunction "GPIO17(ADC2)_B24") (pintype "bidirectional"))
    )
    (net (code "139") (name "Net-(U6-GPIO19(ADC4)-Pad26)") (class "Default")
      (node (ref "U6") (pin "26") (pinfunction "GPIO19(ADC4)_26") (pintype "bidirectional"))
      (node (ref "U6") (pin "B26") (pinfunction "GPIO19(ADC4)_B26") (pintype "bidirectional"))
    )
    (net (code "140") (name "Net-(U6-GPIO20(ADC5)-Pad27)") (class "Default")
      (node (ref "U6") (pin "27") (pinfunction "GPIO20(ADC5)_27") (pintype "bidirectional"))
      (node (ref "U6") (pin "B27") (pinfunction "GPIO20(ADC5)_B27") (pintype "bidirectional"))
    )
    (net (code "141") (name "Net-(U6-GPIO21(ADC6)-Pad28)") (class "Default")
      (node (ref "U6") (pin "28") (pinfunction "GPIO21(ADC6)_28") (pintype "bidirectional"))
      (node (ref "U6") (pin "B28") (pinfunction "GPIO21(ADC6)_B28") (pintype "bidirectional"))
    )
    (net (code "142") (name "Net-(U6-GPIO24(ADC9)-Pad31)") (class "Default")
      (node (ref "U6") (pin "31") (pinfunction "GPIO24(ADC9)_31") (pintype "bidirectional"))
      (node (ref "U6") (pin "B31") (pinfunction "GPIO24(ADC9)_B31") (pintype "bidirectional"))
    )
    (net (code "143") (name "Net-(U6-GPIO25(ADC10)-Pad32)") (class "Default")
      (node (ref "U6") (pin "32") (pinfunction "GPIO25(ADC10)_32") (pintype "bidirectional"))
      (node (ref "U6") (pin "B32") (pinfunction "GPIO25(ADC10)_B32") (pintype "bidirectional"))
    )
    (net (code "144") (name "Net-(U6-GPIO26(SAI2_SD_A)-Pad33)") (class "Default")
      (node (ref "U6") (pin "33") (pinfunction "GPIO26(SAI2_SD_A)_33") (pintype "bidirectional"))
      (node (ref "U6") (pin "B33") (pinfunction "GPIO26(SAI2_SD_A)_B33") (pintype "bidirectional"))
    )
    (net (code "145") (name "Net-(U6-GPIO27(SAI2_FS_B)-Pad34)") (class "Default")
      (node (ref "U6") (pin "34") (pinfunction "GPIO27(SAI2_FS_B)_34") (pintype "bidirectional"))
      (node (ref "U6") (pin "B34") (pinfunction "GPIO27(SAI2_FS_B)_B34") (pintype "bidirectional"))
    )
    (net (code "146") (name "Net-(U7-+3V3_A-Pad21)") (class "Default")
      (node (ref "U7") (pin "21") (pinfunction "+3V3_A_21") (pintype "bidirectional"))
      (node (ref "U7") (pin "B21") (pinfunction "+3V3_A_B21") (pintype "bidirectional"))
    )
    (net (code "147") (name "Net-(U7-AUDIO_IN_L-Pad16)") (class "Default")
      (node (ref "U7") (pin "16") (pinfunction "AUDIO_IN_L_16") (pintype "bidirectional"))
      (node (ref "U7") (pin "B16") (pinfunction "AUDIO_IN_L_B16") (pintype "bidirectional"))
    )
    (net (code "148") (name "Net-(U7-AUDIO_IN_R-Pad17)") (class "Default")
      (node (ref "U7") (pin "17") (pinfunction "AUDIO_IN_R_17") (pintype "bidirectional"))
      (node (ref "U7") (pin "B17") (pinfunction "AUDIO_IN_R_B17") (pintype "bidirectional"))
    )
    (net (code "149") (name "Net-(U7-AUDIO_OUT_R-Pad19)") (class "Default")
      (node (ref "U7") (pin "19") (pinfunction "AUDIO_OUT_R_19") (pintype "bidirectional"))
      (node (ref "U7") (pin "B19") (pinfunction "AUDIO_OUT_R_B19") (pintype "bidirectional"))
    )
    (net (code "150") (name "Net-(U7-GPIO14(USART1_RX)-Pad15)") (class "Default")
      (node (ref "U7") (pin "15") (pinfunction "GPIO14(USART1_RX)_15") (pintype "bidirectional"))
      (node (ref "U7") (pin "B15") (pinfunction "GPIO14(USART1_RX)_B15") (pintype "bidirectional"))
    )
    (net (code "151") (name "Net-(U7-GPIO15(ADC0)-Pad22)") (class "Default")
      (node (ref "U7") (pin "22") (pinfunction "GPIO15(ADC0)_22") (pintype "bidirectional"))
      (node (ref "U7") (pin "B22") (pinfunction "GPIO15(ADC0)_B22") (pintype "bidirectional"))
    )
    (net (code "152") (name "Net-(U7-GPIO16(ADC1)-Pad23)") (class "Default")
      (node (ref "U7") (pin "23") (pinfunction "GPIO16(ADC1)_23") (pintype "bidirectional"))
      (node (ref "U7") (pin "B23") (pinfunction "GPIO16(ADC1)_B23") (pintype "bidirectional"))
    )
    (net (code "153") (name "Net-(U7-GPIO17(ADC2)-Pad24)") (class "Default")
      (node (ref "U7") (pin "24") (pinfunction "GPIO17(ADC2)_24") (pintype "bidirectional"))
      (node (ref "U7") (pin "B24") (pinfunction "GPIO17(ADC2)_B24") (pintype "bidirectional"))
    )
    (net (code "154") (name "Net-(U7-GPIO19(ADC4)-Pad26)") (class "Default")
      (node (ref "U7") (pin "26") (pinfunction "GPIO19(ADC4)_26") (pintype "bidirectional"))
      (node (ref "U7") (pin "B26") (pinfunction "GPIO19(ADC4)_B26") (pintype "bidirectional"))
    )
    (net (code "155") (name "Net-(U7-GPIO20(ADC5)-Pad27)") (class "Default")
      (node (ref "U7") (pin "27") (pinfunction "GPIO20(ADC5)_27") (pintype "bidirectional"))
      (node (ref "U7") (pin "B27") (pinfunction "GPIO20(ADC5)_B27") (pintype "bidirectional"))
    )
    (net (code "156") (name "Net-(U7-GPIO21(ADC6)-Pad28)") (class "Default")
      (node (ref "U7") (pin "28") (pinfunction "GPIO21(ADC6)_28") (pintype "bidirectional"))
      (node (ref "U7") (pin "B28") (pinfunction "GPIO21(ADC6)_B28") (pintype "bidirectional"))
    )
    (net (code "157") (name "Net-(U7-GPIO25(ADC10)-Pad32)") (class "Default")
      (node (ref "U7") (pin "32") (pinfunction "GPIO25(ADC10)_32") (pintype "bidirectional"))
      (node (ref "U7") (pin "B32") (pinfunction "GPIO25(ADC10)_B32") (pintype "bidirectional"))
    )
    (net (code "158") (name "Net-(U7-GPIO26(SAI2_SD_A)-Pad33)") (class "Default")
      (node (ref "U7") (pin "33") (pinfunction "GPIO26(SAI2_SD_A)_33") (pintype "bidirectional"))
      (node (ref "U7") (pin "B33") (pinfunction "GPIO26(SAI2_SD_A)_B33") (pintype "bidirectional"))
    )
    (net (code "159") (name "Net-(U7-GPIO27(SAI2_FS_B)-Pad34)") (class "Default")
      (node (ref "U7") (pin "34") (pinfunction "GPIO27(SAI2_FS_B)_34") (pintype "bidirectional"))
      (node (ref "U7") (pin "B34") (pinfunction "GPIO27(SAI2_FS_B)_B34") (pintype "bidirectional"))
    )
    (net (code "160") (name "Net-(U8-+3V3_A-Pad21)") (class "Default")
      (node (ref "U8") (pin "21") (pinfunction "+3V3_A_21") (pintype "bidirectional"))
      (node (ref "U8") (pin "B21") (pinfunction "+3V3_A_B21") (pintype "bidirectional"))
    )
    (net (code "161") (name "Net-(U8-+3V3_D-Pad38)") (class "Default")
      (node (ref "U8") (pin "35") (pinfunction "GPIO28(ADC11)_35") (pintype "bidirectional"))
      (node (ref "U8") (pin "37") (pinfunction "GPIO30(USB_HS_D+)_37") (pintype "bidirectional"))
      (node (ref "U8") (pin "38") (pinfunction "+3V3_D_38") (pintype "bidirectional"))
      (node (ref "U8") (pin "B35") (pinfunction "GPIO28(ADC11)_B35") (pintype "bidirectional"))
      (node (ref "U8") (pin "B37") (pinfunction "GPIO30(USB_HS_D+)_B37") (pintype "bidirectional"))
      (node (ref "U8") (pin "B38") (pinfunction "+3V3_D_B38") (pintype "bidirectional"))
    )
    (net (code "162") (name "Net-(U8-AUDIO_IN_L-Pad16)") (class "Default")
      (node (ref "U8") (pin "16") (pinfunction "AUDIO_IN_L_16") (pintype "bidirectional"))
      (node (ref "U8") (pin "B16") (pinfunction "AUDIO_IN_L_B16") (pintype "bidirectional"))
    )
    (net (code "163") (name "Net-(U8-AUDIO_IN_R-Pad17)") (class "Default")
      (node (ref "U8") (pin "17") (pinfunction "AUDIO_IN_R_17") (pintype "bidirectional"))
      (node (ref "U8") (pin "B17") (pinfunction "AUDIO_IN_R_B17") (pintype "bidirectional"))
    )
    (net (code "164") (name "Net-(U8-AUDIO_OUT_R-Pad19)") (class "Default")
      (node (ref "U8") (pin "19") (pinfunction "AUDIO_OUT_R_19") (pintype "bidirectional"))
      (node (ref "U8") (pin "B19") (pinfunction "AUDIO_OUT_R_B19") (pintype "bidirectional"))
    )
    (net (code "165") (name "Net-(U8-GPIO1(SDMMC1_D3)-Pad2)") (class "Default")
      (node (ref "U8") (pin "2") (pinfunction "GPIO1(SDMMC1_D3)_2") (pintype "bidirectional"))
      (node (ref "U8") (pin "B2") (pinfunction "GPIO1(SDMMC1_D3)_B2") (pintype "bidirectional"))
    )
    (net (code "166") (name "Net-(U8-GPIO2(SDMMC1_D2)-Pad3)") (class "Default")
      (node (ref "U8") (pin "3") (pinfunction "GPIO2(SDMMC1_D2)_3") (pintype "bidirectional"))
      (node (ref "U8") (pin "B3") (pinfunction "GPIO2(SDMMC1_D2)_B3") (pintype "bidirectional"))
    )
    (net (code "167") (name "Net-(U8-GPIO3(SDMMC1_D1)-Pad4)") (class "Default")
      (node (ref "U8") (pin "4") (pinfunction "GPIO3(SDMMC1_D1)_4") (pintype "bidirectional"))
      (node (ref "U8") (pin "B4") (pinfunction "GPIO3(SDMMC1_D1)_B4") (pintype "bidirectional"))
    )
    (net (code "168") (name "Net-(U8-GPIO4(SDMMC1_D0)-Pad5)") (class "Default")
      (node (ref "U8") (pin "5") (pinfunction "GPIO4(SDMMC1_D0)_5") (pintype "bidirectional"))
      (node (ref "U8") (pin "B5") (pinfunction "GPIO4(SDMMC1_D0)_B5") (pintype "bidirectional"))
    )
    (net (code "169") (name "Net-(U8-GPIO5(SDMMC1_CMD)-Pad6)") (class "Default")
      (node (ref "U8") (pin "6") (pinfunction "GPIO5(SDMMC1_CMD)_6") (pintype "bidirectional"))
      (node (ref "U8") (pin "B6") (pinfunction "GPIO5(SDMMC1_CMD)_B6") (pintype "bidirectional"))
    )
    (net (code "170") (name "Net-(U8-GPIO6(SDMMC1_CK)-Pad7)") (class "Default")
      (node (ref "U8") (pin "7") (pinfunction "GPIO6(SDMMC1_CK)_7") (pintype "bidirectional"))
      (node (ref "U8") (pin "B7") (pinfunction "GPIO6(SDMMC1_CK)_B7") (pintype "bidirectional"))
    )
    (net (code "171") (name "Net-(U8-GPIO9(SPI1_MISO)-Pad10)") (class "Default")
      (node (ref "U8") (pin "10") (pinfunction "GPIO9(SPI1_MISO)_10") (pintype "bidirectional"))
      (node (ref "U8") (pin "B10") (pinfunction "GPIO9(SPI1_MISO)_B10") (pintype "bidirectional"))
    )
    (net (code "172") (name "Net-(U8-GPIO13(USART1_TX)-Pad14)") (class "Default")
      (node (ref "U8") (pin "14") (pinfunction "GPIO13(USART1_TX)_14") (pintype "bidirectional"))
      (node (ref "U8") (pin "B14") (pinfunction "GPIO13(USART1_TX)_B14") (pintype "bidirectional"))
    )
    (net (code "173") (name "Net-(U8-GPIO14(USART1_RX)-Pad15)") (class "Default")
      (node (ref "U8") (pin "15") (pinfunction "GPIO14(USART1_RX)_15") (pintype "bidirectional"))
      (node (ref "U8") (pin "B15") (pinfunction "GPIO14(USART1_RX)_B15") (pintype "bidirectional"))
    )
    (net (code "174") (name "Net-(U8-GPIO15(ADC0)-Pad22)") (class "Default")
      (node (ref "U8") (pin "22") (pinfunction "GPIO15(ADC0)_22") (pintype "bidirectional"))
      (node (ref "U8") (pin "B22") (pinfunction "GPIO15(ADC0)_B22") (pintype "bidirectional"))
    )
    (net (code "175") (name "Net-(U8-GPIO16(ADC1)-Pad23)") (class "Default")
      (node (ref "U8") (pin "23") (pinfunction "GPIO16(ADC1)_23") (pintype "bidirectional"))
      (node (ref "U8") (pin "B23") (pinfunction "GPIO16(ADC1)_B23") (pintype "bidirectional"))
    )
    (net (code "176") (name "Net-(U8-GPIO17(ADC2)-Pad24)") (class "Default")
      (node (ref "U8") (pin "24") (pinfunction "GPIO17(ADC2)_24") (pintype "bidirectional"))
      (node (ref "U8") (pin "B24") (pinfunction "GPIO17(ADC2)_B24") (pintype "bidirectional"))
    )
    (net (code "177") (name "Net-(U8-GPIO19(ADC4)-Pad26)") (class "Default")
      (node (ref "U8") (pin "26") (pinfunction "GPIO19(ADC4)_26") (pintype "bidirectional"))
      (node (ref "U8") (pin "B26") (pinfunction "GPIO19(ADC4)_B26") (pintype "bidirectional"))
    )
    (net (code "178") (name "Net-(U8-GPIO20(ADC5)-Pad27)") (class "Default")
      (node (ref "U8") (pin "27") (pinfunction "GPIO20(ADC5)_27") (pintype "bidirectional"))
      (node (ref "U8") (pin "B27") (pinfunction "GPIO20(ADC5)_B27") (pintype "bidirectional"))
    )
    (net (code "179") (name "Net-(U8-GPIO21(ADC6)-Pad28)") (class "Default")
      (node (ref "U8") (pin "28") (pinfunction "GPIO21(ADC6)_28") (pintype "bidirectional"))
      (node (ref "U8") (pin "B28") (pinfunction "GPIO21(ADC6)_B28") (pintype "bidirectional"))
    )
    (net (code "180") (name "Net-(U8-GPIO24(ADC9)-Pad31)") (class "Default")
      (node (ref "U8") (pin "31") (pinfunction "GPIO24(ADC9)_31") (pintype "bidirectional"))
      (node (ref "U8") (pin "B31") (pinfunction "GPIO24(ADC9)_B31") (pintype "bidirectional"))
    )
    (net (code "181") (name "Net-(U8-GPIO25(ADC10)-Pad32)") (class "Default")
      (node (ref "U8") (pin "32") (pinfunction "GPIO25(ADC10)_32") (pintype "bidirectional"))
      (node (ref "U8") (pin "B32") (pinfunction "GPIO25(ADC10)_B32") (pintype "bidirectional"))
    )
    (net (code "182") (name "Net-(U8-GPIO26(SAI2_SD_A)-Pad33)") (class "Default")
      (node (ref "U8") (pin "33") (pinfunction "GPIO26(SAI2_SD_A)_33") (pintype "bidirectional"))
      (node (ref "U8") (pin "B33") (pinfunction "GPIO26(SAI2_SD_A)_B33") (pintype "bidirectional"))
    )
    (net (code "183") (name "Net-(U8-GPIO27(SAI2_FS_B)-Pad34)") (class "Default")
      (node (ref "U8") (pin "34") (pinfunction "GPIO27(SAI2_FS_B)_34") (pintype "bidirectional"))
      (node (ref "U8") (pin "B34") (pinfunction "GPIO27(SAI2_FS_B)_B34") (pintype "bidirectional"))
    )
    (net (code "184") (name "Net-(U9-+3V3_A-Pad21)") (class "Default")
      (node (ref "U9") (pin "21") (pinfunction "+3V3_A_21") (pintype "bidirectional"))
      (node (ref "U9") (pin "B21") (pinfunction "+3V3_A_B21") (pintype "bidirectional"))
    )
    (net (code "185") (name "Net-(U9-AUDIO_IN_L-Pad16)") (class "Default")
      (node (ref "U9") (pin "16") (pinfunction "AUDIO_IN_L_16") (pintype "bidirectional"))
      (node (ref "U9") (pin "B16") (pinfunction "AUDIO_IN_L_B16") (pintype "bidirectional"))
    )
    (net (code "186") (name "Net-(U9-AUDIO_IN_R-Pad17)") (class "Default")
      (node (ref "U9") (pin "17") (pinfunction "AUDIO_IN_R_17") (pintype "bidirectional"))
      (node (ref "U9") (pin "B17") (pinfunction "AUDIO_IN_R_B17") (pintype "bidirectional"))
    )
    (net (code "187") (name "Net-(U9-AUDIO_OUT_R-Pad19)") (class "Default")
      (node (ref "U9") (pin "19") (pinfunction "AUDIO_OUT_R_19") (pintype "bidirectional"))
      (node (ref "U9") (pin "B19") (pinfunction "AUDIO_OUT_R_B19") (pintype "bidirectional"))
    )
    (net (code "188") (name "Net-(U9-GPIO1(SDMMC1_D3)-Pad2)") (class "Default")
      (node (ref "U9") (pin "2") (pinfunction "GPIO1(SDMMC1_D3)_2") (pintype "bidirectional"))
      (node (ref "U9") (pin "B2") (pinfunction "GPIO1(SDMMC1_D3)_B2") (pintype "bidirectional"))
    )
    (net (code "189") (name "Net-(U9-GPIO2(SDMMC1_D2)-Pad3)") (class "Default")
      (node (ref "U9") (pin "3") (pinfunction "GPIO2(SDMMC1_D2)_3") (pintype "bidirectional"))
      (node (ref "U9") (pin "B3") (pinfunction "GPIO2(SDMMC1_D2)_B3") (pintype "bidirectional"))
    )
    (net (code "190") (name "Net-(U9-GPIO3(SDMMC1_D1)-Pad4)") (class "Default")
      (node (ref "U9") (pin "4") (pinfunction "GPIO3(SDMMC1_D1)_4") (pintype "bidirectional"))
      (node (ref "U9") (pin "B4") (pinfunction "GPIO3(SDMMC1_D1)_B4") (pintype "bidirectional"))
    )
    (net (code "191") (name "Net-(U9-GPIO4(SDMMC1_D0)-Pad5)") (class "Default")
      (node (ref "U9") (pin "5") (pinfunction "GPIO4(SDMMC1_D0)_5") (pintype "bidirectional"))
      (node (ref "U9") (pin "B5") (pinfunction "GPIO4(SDMMC1_D0)_B5") (pintype "bidirectional"))
    )
    (net (code "192") (name "Net-(U9-GPIO5(SDMMC1_CMD)-Pad6)") (class "Default")
      (node (ref "U9") (pin "6") (pinfunction "GPIO5(SDMMC1_CMD)_6") (pintype "bidirectional"))
      (node (ref "U9") (pin "B6") (pinfunction "GPIO5(SDMMC1_CMD)_B6") (pintype "bidirectional"))
    )
    (net (code "193") (name "Net-(U9-GPIO6(SDMMC1_CK)-Pad7)") (class "Default")
      (node (ref "U9") (pin "7") (pinfunction "GPIO6(SDMMC1_CK)_7") (pintype "bidirectional"))
      (node (ref "U9") (pin "B7") (pinfunction "GPIO6(SDMMC1_CK)_B7") (pintype "bidirectional"))
    )
    (net (code "194") (name "Net-(U9-GPIO9(SPI1_MISO)-Pad10)") (class "Default")
      (node (ref "U9") (pin "10") (pinfunction "GPIO9(SPI1_MISO)_10") (pintype "bidirectional"))
      (node (ref "U9") (pin "B10") (pinfunction "GPIO9(SPI1_MISO)_B10") (pintype "bidirectional"))
    )
    (net (code "195") (name "Net-(U9-GPIO13(USART1_TX)-Pad14)") (class "Default")
      (node (ref "U9") (pin "14") (pinfunction "GPIO13(USART1_TX)_14") (pintype "bidirectional"))
      (node (ref "U9") (pin "B14") (pinfunction "GPIO13(USART1_TX)_B14") (pintype "bidirectional"))
    )
    (net (code "196") (name "Net-(U9-GPIO14(USART1_RX)-Pad15)") (class "Default")
      (node (ref "U9") (pin "15") (pinfunction "GPIO14(USART1_RX)_15") (pintype "bidirectional"))
      (node (ref "U9") (pin "B15") (pinfunction "GPIO14(USART1_RX)_B15") (pintype "bidirectional"))
    )
    (net (code "197") (name "Net-(U9-GPIO15(ADC0)-Pad22)") (class "Default")
      (node (ref "U9") (pin "22") (pinfunction "GPIO15(ADC0)_22") (pintype "bidirectional"))
      (node (ref "U9") (pin "B22") (pinfunction "GPIO15(ADC0)_B22") (pintype "bidirectional"))
    )
    (net (code "198") (name "Net-(U9-GPIO16(ADC1)-Pad23)") (class "Default")
      (node (ref "U9") (pin "23") (pinfunction "GPIO16(ADC1)_23") (pintype "bidirectional"))
      (node (ref "U9") (pin "B23") (pinfunction "GPIO16(ADC1)_B23") (pintype "bidirectional"))
    )
    (net (code "199") (name "Net-(U9-GPIO17(ADC2)-Pad24)") (class "Default")
      (node (ref "U9") (pin "24") (pinfunction "GPIO17(ADC2)_24") (pintype "bidirectional"))
      (node (ref "U9") (pin "B24") (pinfunction "GPIO17(ADC2)_B24") (pintype "bidirectional"))
    )
    (net (code "200") (name "Net-(U9-GPIO19(ADC4)-Pad26)") (class "Default")
      (node (ref "U9") (pin "26") (pinfunction "GPIO19(ADC4)_26") (pintype "bidirectional"))
      (node (ref "U9") (pin "B26") (pinfunction "GPIO19(ADC4)_B26") (pintype "bidirectional"))
    )
    (net (code "201") (name "Net-(U9-GPIO20(ADC5)-Pad27)") (class "Default")
      (node (ref "U9") (pin "27") (pinfunction "GPIO20(ADC5)_27") (pintype "bidirectional"))
      (node (ref "U9") (pin "B27") (pinfunction "GPIO20(ADC5)_B27") (pintype "bidirectional"))
    )
    (net (code "202") (name "Net-(U9-GPIO21(ADC6)-Pad28)") (class "Default")
      (node (ref "U9") (pin "28") (pinfunction "GPIO21(ADC6)_28") (pintype "bidirectional"))
      (node (ref "U9") (pin "B28") (pinfunction "GPIO21(ADC6)_B28") (pintype "bidirectional"))
    )
    (net (code "203") (name "Net-(U9-GPIO24(ADC9)-Pad31)") (class "Default")
      (node (ref "U9") (pin "31") (pinfunction "GPIO24(ADC9)_31") (pintype "bidirectional"))
      (node (ref "U9") (pin "B31") (pinfunction "GPIO24(ADC9)_B31") (pintype "bidirectional"))
    )
    (net (code "204") (name "Net-(U9-GPIO25(ADC10)-Pad32)") (class "Default")
      (node (ref "U9") (pin "32") (pinfunction "GPIO25(ADC10)_32") (pintype "bidirectional"))
      (node (ref "U9") (pin "B32") (pinfunction "GPIO25(ADC10)_B32") (pintype "bidirectional"))
    )
    (net (code "205") (name "Net-(U9-GPIO26(SAI2_SD_A)-Pad33)") (class "Default")
      (node (ref "U9") (pin "33") (pinfunction "GPIO26(SAI2_SD_A)_33") (pintype "bidirectional"))
      (node (ref "U9") (pin "B33") (pinfunction "GPIO26(SAI2_SD_A)_B33") (pintype "bidirectional"))
    )
    (net (code "206") (name "Net-(U9-GPIO27(SAI2_FS_B)-Pad34)") (class "Default")
      (node (ref "U9") (pin "34") (pinfunction "GPIO27(SAI2_FS_B)_34") (pintype "bidirectional"))
      (node (ref "U9") (pin "B34") (pinfunction "GPIO27(SAI2_FS_B)_B34") (pintype "bidirectional"))
    )
    (net (code "207") (name "Net-(U10-+3V3_A-Pad21)") (class "Default")
      (node (ref "U10") (pin "21") (pinfunction "+3V3_A_21") (pintype "bidirectional"))
      (node (ref "U10") (pin "B21") (pinfunction "+3V3_A_B21") (pintype "bidirectional"))
    )
    (net (code "208") (name "Net-(U10-+3V3_D-Pad38)") (class "Default")
      (node (ref "U10") (pin "37") (pinfunction "GPIO30(USB_HS_D+)_37") (pintype "bidirectional"))
      (node (ref "U10") (pin "38") (pinfunction "+3V3_D_38") (pintype "bidirectional"))
      (node (ref "U10") (pin "B37") (pinfunction "GPIO30(USB_HS_D+)_B37") (pintype "bidirectional"))
      (node (ref "U10") (pin "B38") (pinfunction "+3V3_D_B38") (pintype "bidirectional"))
    )
    (net (code "209") (name "Net-(U10-AUDIO_IN_L-Pad16)") (class "Default")
      (node (ref "U10") (pin "16") (pinfunction "AUDIO_IN_L_16") (pintype "bidirectional"))
      (node (ref "U10") (pin "B16") (pinfunction "AUDIO_IN_L_B16") (pintype "bidirectional"))
    )
    (net (code "210") (name "Net-(U10-AUDIO_IN_R-Pad17)") (class "Default")
      (node (ref "U10") (pin "17") (pinfunction "AUDIO_IN_R_17") (pintype "bidirectional"))
      (node (ref "U10") (pin "B17") (pinfunction "AUDIO_IN_R_B17") (pintype "bidirectional"))
    )
    (net (code "211") (name "Net-(U10-AUDIO_OUT_R-Pad19)") (class "Default")
      (node (ref "U10") (pin "19") (pinfunction "AUDIO_OUT_R_19") (pintype "bidirectional"))
      (node (ref "U10") (pin "B19") (pinfunction "AUDIO_OUT_R_B19") (pintype "bidirectional"))
    )
    (net (code "212") (name "Net-(U10-GPIO1(SDMMC1_D3)-Pad2)") (class "Default")
      (node (ref "U10") (pin "2") (pinfunction "GPIO1(SDMMC1_D3)_2") (pintype "bidirectional"))
      (node (ref "U10") (pin "B2") (pinfunction "GPIO1(SDMMC1_D3)_B2") (pintype "bidirectional"))
    )
    (net (code "213") (name "Net-(U10-GPIO2(SDMMC1_D2)-Pad3)") (class "Default")
      (node (ref "U10") (pin "3") (pinfunction "GPIO2(SDMMC1_D2)_3") (pintype "bidirectional"))
      (node (ref "U10") (pin "B3") (pinfunction "GPIO2(SDMMC1_D2)_B3") (pintype "bidirectional"))
    )
    (net (code "214") (name "Net-(U10-GPIO3(SDMMC1_D1)-Pad4)") (class "Default")
      (node (ref "U10") (pin "4") (pinfunction "GPIO3(SDMMC1_D1)_4") (pintype "bidirectional"))
      (node (ref "U10") (pin "B4") (pinfunction "GPIO3(SDMMC1_D1)_B4") (pintype "bidirectional"))
    )
    (net (code "215") (name "Net-(U10-GPIO4(SDMMC1_D0)-Pad5)") (class "Default")
      (node (ref "U10") (pin "5") (pinfunction "GPIO4(SDMMC1_D0)_5") (pintype "bidirectional"))
      (node (ref "U10") (pin "B5") (pinfunction "GPIO4(SDMMC1_D0)_B5") (pintype "bidirectional"))
    )
    (net (code "216") (name "Net-(U10-GPIO5(SDMMC1_CMD)-Pad6)") (class "Default")
      (node (ref "U10") (pin "6") (pinfunction "GPIO5(SDMMC1_CMD)_6") (pintype "bidirectional"))
      (node (ref "U10") (pin "B6") (pinfunction "GPIO5(SDMMC1_CMD)_B6") (pintype "bidirectional"))
    )
    (net (code "217") (name "Net-(U10-GPIO6(SDMMC1_CK)-Pad7)") (class "Default")
      (node (ref "U10") (pin "7") (pinfunction "GPIO6(SDMMC1_CK)_7") (pintype "bidirectional"))
      (node (ref "U10") (pin "B7") (pinfunction "GPIO6(SDMMC1_CK)_B7") (pintype "bidirectional"))
    )
    (net (code "218") (name "Net-(U10-GPIO9(SPI1_MISO)-Pad10)") (class "Default")
      (node (ref "U10") (pin "10") (pinfunction "GPIO9(SPI1_MISO)_10") (pintype "bidirectional"))
      (node (ref "U10") (pin "B10") (pinfunction "GPIO9(SPI1_MISO)_B10") (pintype "bidirectional"))
    )
    (net (code "219") (name "Net-(U10-GPIO13(USART1_TX)-Pad14)") (class "Default")
      (node (ref "U10") (pin "14") (pinfunction "GPIO13(USART1_TX)_14") (pintype "bidirectional"))
      (node (ref "U10") (pin "B14") (pinfunction "GPIO13(USART1_TX)_B14") (pintype "bidirectional"))
    )
    (net (code "220") (name "Net-(U10-GPIO14(USART1_RX)-Pad15)") (class "Default")
      (node (ref "U10") (pin "15") (pinfunction "GPIO14(USART1_RX)_15") (pintype "bidirectional"))
      (node (ref "U10") (pin "B15") (pinfunction "GPIO14(USART1_RX)_B15") (pintype "bidirectional"))
    )
    (net (code "221") (name "Net-(U10-GPIO15(ADC0)-Pad22)") (class "Default")
      (node (ref "U10") (pin "22") (pinfunction "GPIO15(ADC0)_22") (pintype "bidirectional"))
      (node (ref "U10") (pin "B22") (pinfunction "GPIO15(ADC0)_B22") (pintype "bidirectional"))
    )
    (net (code "222") (name "Net-(U10-GPIO16(ADC1)-Pad23)") (class "Default")
      (node (ref "U10") (pin "23") (pinfunction "GPIO16(ADC1)_23") (pintype "bidirectional"))
      (node (ref "U10") (pin "B23") (pinfunction "GPIO16(ADC1)_B23") (pintype "bidirectional"))
    )
    (net (code "223") (name "Net-(U10-GPIO17(ADC2)-Pad24)") (class "Default")
      (node (ref "U10") (pin "24") (pinfunction "GPIO17(ADC2)_24") (pintype "bidirectional"))
      (node (ref "U10") (pin "B24") (pinfunction "GPIO17(ADC2)_B24") (pintype "bidirectional"))
    )
    (net (code "224") (name "Net-(U10-GPIO19(ADC4)-Pad26)") (class "Default")
      (node (ref "U10") (pin "26") (pinfunction "GPIO19(ADC4)_26") (pintype "bidirectional"))
      (node (ref "U10") (pin "B26") (pinfunction "GPIO19(ADC4)_B26") (pintype "bidirectional"))
    )
    (net (code "225") (name "Net-(U10-GPIO20(ADC5)-Pad27)") (class "Default")
      (node (ref "U10") (pin "27") (pinfunction "GPIO20(ADC5)_27") (pintype "bidirectional"))
      (node (ref "U10") (pin "B27") (pinfunction "GPIO20(ADC5)_B27") (pintype "bidirectional"))
    )
    (net (code "226") (name "Net-(U10-GPIO21(ADC6)-Pad28)") (class "Default")
      (node (ref "U10") (pin "28") (pinfunction "GPIO21(ADC6)_28") (pintype "bidirectional"))
      (node (ref "U10") (pin "B28") (pinfunction "GPIO21(ADC6)_B28") (pintype "bidirectional"))
    )
    (net (code "227") (name "Net-(U10-GPIO24(ADC9)-Pad31)") (class "Default")
      (node (ref "U10") (pin "31") (pinfunction "GPIO24(ADC9)_31") (pintype "bidirectional"))
      (node (ref "U10") (pin "B31") (pinfunction "GPIO24(ADC9)_B31") (pintype "bidirectional"))
    )
    (net (code "228") (name "Net-(U10-GPIO25(ADC10)-Pad32)") (class "Default")
      (node (ref "U10") (pin "32") (pinfunction "GPIO25(ADC10)_32") (pintype "bidirectional"))
      (node (ref "U10") (pin "B32") (pinfunction "GPIO25(ADC10)_B32") (pintype "bidirectional"))
    )
    (net (code "229") (name "Net-(U10-GPIO26(SAI2_SD_A)-Pad33)") (class "Default")
      (node (ref "U10") (pin "33") (pinfunction "GPIO26(SAI2_SD_A)_33") (pintype "bidirectional"))
      (node (ref "U10") (pin "B33") (pinfunction "GPIO26(SAI2_SD_A)_B33") (pintype "bidirectional"))
    )
    (net (code "230") (name "Net-(U10-GPIO27(SAI2_FS_B)-Pad34)") (class "Default")
      (node (ref "U10") (pin "34") (pinfunction "GPIO27(SAI2_FS_B)_34") (pintype "bidirectional"))
      (node (ref "U10") (pin "B34") (pinfunction "GPIO27(SAI2_FS_B)_B34") (pintype "bidirectional"))
    )
    (net (code "231") (name "Net-(U11-+3V3_A-Pad21)") (class "Default")
      (node (ref "U11") (pin "21") (pinfunction "+3V3_A_21") (pintype "bidirectional"))
      (node (ref "U11") (pin "B21") (pinfunction "+3V3_A_B21") (pintype "bidirectional"))
    )
    (net (code "232") (name "Net-(U11-+3V3_D-Pad38)") (class "Default")
      (node (ref "U11") (pin "35") (pinfunction "GPIO28(ADC11)_35") (pintype "bidirectional"))
      (node (ref "U11") (pin "37") (pinfunction "GPIO30(USB_HS_D+)_37") (pintype "bidirectional"))
      (node (ref "U11") (pin "38") (pinfunction "+3V3_D_38") (pintype "bidirectional"))
      (node (ref "U11") (pin "B35") (pinfunction "GPIO28(ADC11)_B35") (pintype "bidirectional"))
      (node (ref "U11") (pin "B37") (pinfunction "GPIO30(USB_HS_D+)_B37") (pintype "bidirectional"))
      (node (ref "U11") (pin "B38") (pinfunction "+3V3_D_B38") (pintype "bidirectional"))
    )
    (net (code "233") (name "Net-(U11-AUDIO_IN_L-Pad16)") (class "Default")
      (node (ref "U11") (pin "16") (pinfunction "AUDIO_IN_L_16") (pintype "bidirectional"))
      (node (ref "U11") (pin "B16") (pinfunction "AUDIO_IN_L_B16") (pintype "bidirectional"))
    )
    (net (code "234") (name "Net-(U11-AUDIO_IN_R-Pad17)") (class "Default")
      (node (ref "U11") (pin "17") (pinfunction "AUDIO_IN_R_17") (pintype "bidirectional"))
      (node (ref "U11") (pin "B17") (pinfunction "AUDIO_IN_R_B17") (pintype "bidirectional"))
    )
    (net (code "235") (name "Net-(U11-AUDIO_OUT_R-Pad19)") (class "Default")
      (node (ref "U11") (pin "19") (pinfunction "AUDIO_OUT_R_19") (pintype "bidirectional"))
      (node (ref "U11") (pin "B19") (pinfunction "AUDIO_OUT_R_B19") (pintype "bidirectional"))
    )
    (net (code "236") (name "Net-(U11-GPIO1(SDMMC1_D3)-Pad2)") (class "Default")
      (node (ref "U11") (pin "2") (pinfunction "GPIO1(SDMMC1_D3)_2") (pintype "bidirectional"))
      (node (ref "U11") (pin "B2") (pinfunction "GPIO1(SDMMC1_D3)_B2") (pintype "bidirectional"))
    )
    (net (code "237") (name "Net-(U11-GPIO2(SDMMC1_D2)-Pad3)") (class "Default")
      (node (ref "U11") (pin "3") (pinfunction "GPIO2(SDMMC1_D2)_3") (pintype "bidirectional"))
      (node (ref "U11") (pin "B3") (pinfunction "GPIO2(SDMMC1_D2)_B3") (pintype "bidirectional"))
    )
    (net (code "238") (name "Net-(U11-GPIO3(SDMMC1_D1)-Pad4)") (class "Default")
      (node (ref "U11") (pin "4") (pinfunction "GPIO3(SDMMC1_D1)_4") (pintype "bidirectional"))
      (node (ref "U11") (pin "B4") (pinfunction "GPIO3(SDMMC1_D1)_B4") (pintype "bidirectional"))
    )
    (net (code "239") (name "Net-(U11-GPIO4(SDMMC1_D0)-Pad5)") (class "Default")
      (node (ref "U11") (pin "5") (pinfunction "GPIO4(SDMMC1_D0)_5") (pintype "bidirectional"))
      (node (ref "U11") (pin "B5") (pinfunction "GPIO4(SDMMC1_D0)_B5") (pintype "bidirectional"))
    )
    (net (code "240") (name "Net-(U11-GPIO5(SDMMC1_CMD)-Pad6)") (class "Default")
      (node (ref "U11") (pin "6") (pinfunction "GPIO5(SDMMC1_CMD)_6") (pintype "bidirectional"))
      (node (ref "U11") (pin "B6") (pinfunction "GPIO5(SDMMC1_CMD)_B6") (pintype "bidirectional"))
    )
    (net (code "241") (name "Net-(U11-GPIO6(SDMMC1_CK)-Pad7)") (class "Default")
      (node (ref "U11") (pin "7") (pinfunction "GPIO6(SDMMC1_CK)_7") (pintype "bidirectional"))
      (node (ref "U11") (pin "B7") (pinfunction "GPIO6(SDMMC1_CK)_B7") (pintype "bidirectional"))
    )
    (net (code "242") (name "Net-(U11-GPIO9(SPI1_MISO)-Pad10)") (class "Default")
      (node (ref "U11") (pin "10") (pinfunction "GPIO9(SPI1_MISO)_10") (pintype "bidirectional"))
      (node (ref "U11") (pin "B10") (pinfunction "GPIO9(SPI1_MISO)_B10") (pintype "bidirectional"))
    )
    (net (code "243") (name "Net-(U11-GPIO13(USART1_TX)-Pad14)") (class "Default")
      (node (ref "U11") (pin "14") (pinfunction "GPIO13(USART1_TX)_14") (pintype "bidirectional"))
      (node (ref "U11") (pin "B14") (pinfunction "GPIO13(USART1_TX)_B14") (pintype "bidirectional"))
    )
    (net (code "244") (name "Net-(U11-GPIO14(USART1_RX)-Pad15)") (class "Default")
      (node (ref "U11") (pin "15") (pinfunction "GPIO14(USART1_RX)_15") (pintype "bidirectional"))
      (node (ref "U11") (pin "B15") (pinfunction "GPIO14(USART1_RX)_B15") (pintype "bidirectional"))
    )
    (net (code "245") (name "Net-(U11-GPIO15(ADC0)-Pad22)") (class "Default")
      (node (ref "U11") (pin "22") (pinfunction "GPIO15(ADC0)_22") (pintype "bidirectional"))
      (node (ref "U11") (pin "B22") (pinfunction "GPIO15(ADC0)_B22") (pintype "bidirectional"))
    )
    (net (code "246") (name "Net-(U11-GPIO16(ADC1)-Pad23)") (class "Default")
      (node (ref "U11") (pin "23") (pinfunction "GPIO16(ADC1)_23") (pintype "bidirectional"))
      (node (ref "U11") (pin "B23") (pinfunction "GPIO16(ADC1)_B23") (pintype "bidirectional"))
    )
    (net (code "247") (name "Net-(U11-GPIO17(ADC2)-Pad24)") (class "Default")
      (node (ref "U11") (pin "24") (pinfunction "GPIO17(ADC2)_24") (pintype "bidirectional"))
      (node (ref "U11") (pin "B24") (pinfunction "GPIO17(ADC2)_B24") (pintype "bidirectional"))
    )
    (net (code "248") (name "Net-(U11-GPIO19(ADC4)-Pad26)") (class "Default")
      (node (ref "U11") (pin "26") (pinfunction "GPIO19(ADC4)_26") (pintype "bidirectional"))
      (node (ref "U11") (pin "B26") (pinfunction "GPIO19(ADC4)_B26") (pintype "bidirectional"))
    )
    (net (code "249") (name "Net-(U11-GPIO20(ADC5)-Pad27)") (class "Default")
      (node (ref "U11") (pin "27") (pinfunction "GPIO20(ADC5)_27") (pintype "bidirectional"))
      (node (ref "U11") (pin "B27") (pinfunction "GPIO20(ADC5)_B27") (pintype "bidirectional"))
    )
    (net (code "250") (name "Net-(U11-GPIO21(ADC6)-Pad28)") (class "Default")
      (node (ref "U11") (pin "28") (pinfunction "GPIO21(ADC6)_28") (pintype "bidirectional"))
      (node (ref "U11") (pin "B28") (pinfunction "GPIO21(ADC6)_B28") (pintype "bidirectional"))
    )
    (net (code "251") (name "Net-(U11-GPIO24(ADC9)-Pad31)") (class "Default")
      (node (ref "U11") (pin "31") (pinfunction "GPIO24(ADC9)_31") (pintype "bidirectional"))
      (node (ref "U11") (pin "B31") (pinfunction "GPIO24(ADC9)_B31") (pintype "bidirectional"))
    )
    (net (code "252") (name "Net-(U11-GPIO25(ADC10)-Pad32)") (class "Default")
      (node (ref "U11") (pin "32") (pinfunction "GPIO25(ADC10)_32") (pintype "bidirectional"))
      (node (ref "U11") (pin "B32") (pinfunction "GPIO25(ADC10)_B32") (pintype "bidirectional"))
    )
    (net (code "253") (name "Net-(U11-GPIO26(SAI2_SD_A)-Pad33)") (class "Default")
      (node (ref "U11") (pin "33") (pinfunction "GPIO26(SAI2_SD_A)_33") (pintype "bidirectional"))
      (node (ref "U11") (pin "B33") (pinfunction "GPIO26(SAI2_SD_A)_B33") (pintype "bidirectional"))
    )
    (net (code "254") (name "Net-(U11-GPIO27(SAI2_FS_B)-Pad34)") (class "Default")
      (node (ref "U11") (pin "34") (pinfunction "GPIO27(SAI2_FS_B)_34") (pintype "bidirectional"))
      (node (ref "U11") (pin "B34") (pinfunction "GPIO27(SAI2_FS_B)_B34") (pintype "bidirectional"))
    )
    (net (code "255") (name "Net-(X1C-KL)") (class "Default")
      (node (ref "R27") (pin "2") (pinfunction "2_2") (pintype "passive"))
      (node (ref "X1") (pin "11") (pinfunction "KL_11") (pintype "passive"))
    )
    (net (code "256") (name "OUT1") (class "Default")
      (node (ref "C25") (pin "1") (pinfunction "1_1") (pintype "passive"))
      (node (ref "U7") (pin "18") (pinfunction "AUDIO_OUT_L_18") (pintype "bidirectional"))
      (node (ref "U7") (pin "B18") (pinfunction "AUDIO_OUT_L_B18") (pintype "bidirectional"))
    )
    (net (code "257") (name "OUT2") (class "Default")
      (node (ref "C21") (pin "1") (pinfunction "1_1") (pintype "passive"))
      (node (ref "U3") (pin "18") (pinfunction "AUDIO_OUT_L_18") (pintype "bidirectional"))
      (node (ref "U3") (pin "B18") (pinfunction "AUDIO_OUT_L_B18") (pintype "bidirectional"))
    )
    (net (code "258") (name "OUT3") (class "Default")
      (node (ref "C26") (pin "1") (pinfunction "1_1") (pintype "passive"))
      (node (ref "U2") (pin "18") (pinfunction "AUDIO_OUT_L_18") (pintype "bidirectional"))
      (node (ref "U2") (pin "B18") (pinfunction "AUDIO_OUT_L_B18") (pintype "bidirectional"))
      (node (ref "U4") (pin "18") (pinfunction "AUDIO_OUT_L_18") (pintype "bidirectional"))
      (node (ref "U4") (pin "B18") (pinfunction "AUDIO_OUT_L_B18") (pintype "bidirectional"))
    )
    (net (code "259") (name "OUT4") (class "Default")
      (node (ref "C27") (pin "1") (pinfunction "1_1") (pintype "passive"))
      (node (ref "U5") (pin "18") (pinfunction "AUDIO_OUT_L_18") (pintype "bidirectional"))
      (node (ref "U5") (pin "B18") (pinfunction "AUDIO_OUT_L_B18") (pintype "bidirectional"))
      (node (ref "U9") (pin "18") (pinfunction "AUDIO_OUT_L_18") (pintype "bidirectional"))
      (node (ref "U9") (pin "B18") (pinfunction "AUDIO_OUT_L_B18") (pintype "bidirectional"))
    )
    (net (code "260") (name "OUT5") (class "Default")
      (node (ref "C29") (pin "1") (pinfunction "1_1") (pintype "passive"))
      (node (ref "U10") (pin "18") (pinfunction "AUDIO_OUT_L_18") (pintype "bidirectional"))
      (node (ref "U10") (pin "B18") (pinfunction "AUDIO_OUT_L_B18") (pintype "bidirectional"))
      (node (ref "U6") (pin "18") (pinfunction "AUDIO_OUT_L_18") (pintype "bidirectional"))
      (node (ref "U6") (pin "B18") (pinfunction "AUDIO_OUT_L_B18") (pintype "bidirectional"))
    )
    (net (code "261") (name "OUT6") (class "Default")
      (node (ref "C31") (pin "1") (pinfunction "1_1") (pintype "passive"))
      (node (ref "U11") (pin "18") (pinfunction "AUDIO_OUT_L_18") (pintype "bidirectional"))
      (node (ref "U11") (pin "B18") (pinfunction "AUDIO_OUT_L_B18") (pintype "bidirectional"))
      (node (ref "U8") (pin "18") (pinfunction "AUDIO_OUT_L_18") (pintype "bidirectional"))
      (node (ref "U8") (pin "B18") (pinfunction "AUDIO_OUT_L_B18") (pintype "bidirectional"))
    )
    (net (code "262") (name "PA1_SD_DETECT") (class "Default")
      (node (ref "J2") (pin "9") (pinfunction "DET_9") (pintype "bidirectional"))
      (node (ref "U3") (pin "31") (pinfunction "GPIO24(ADC9)_31") (pintype "bidirectional"))
      (node (ref "U3") (pin "B31") (pinfunction "GPIO24(ADC9)_B31") (pintype "bidirectional"))
      (node (ref "U7") (pin "31") (pinfunction "GPIO24(ADC9)_31") (pintype "bidirectional"))
      (node (ref "U7") (pin "B31") (pinfunction "GPIO24(ADC9)_B31") (pintype "bidirectional"))
    )
    (net (code "263") (name "PULLUPED") (class "Default")
      (node (ref "U5") (pin "35") (pinfunction "GPIO28(ADC11)_35") (pintype "bidirectional"))
      (node (ref "U5") (pin "36") (pinfunction "GPIO29(USB_HS_D_-)_36") (pintype "bidirectional"))
      (node (ref "U5") (pin "38") (pinfunction "+3V3_D_38") (pintype "bidirectional"))
      (node (ref "U5") (pin "B35") (pinfunction "GPIO28(ADC11)_B35") (pintype "bidirectional"))
      (node (ref "U5") (pin "B36") (pinfunction "GPIO29(USB_HS_D_-)_B36") (pintype "bidirectional"))
      (node (ref "U5") (pin "B38") (pinfunction "+3V3_D_B38") (pintype "bidirectional"))
      (node (ref "U9") (pin "35") (pinfunction "GPIO28(ADC11)_35") (pintype "bidirectional"))
      (node (ref "U9") (pin "36") (pinfunction "GPIO29(USB_HS_D_-)_36") (pintype "bidirectional"))
      (node (ref "U9") (pin "38") (pinfunction "+3V3_D_38") (pintype "bidirectional"))
      (node (ref "U9") (pin "B35") (pinfunction "GPIO28(ADC11)_B35") (pintype "bidirectional"))
      (node (ref "U9") (pin "B36") (pinfunction "GPIO29(USB_HS_D_-)_B36") (pintype "bidirectional"))
      (node (ref "U9") (pin "B38") (pinfunction "+3V3_D_B38") (pintype "bidirectional"))
    )
    (net (code "264") (name "PULLUPED2") (class "Default")
      (node (ref "U2") (pin "36") (pinfunction "GPIO29(USB_HS_D_-)_36") (pintype "bidirectional"))
      (node (ref "U2") (pin "38") (pinfunction "+3V3_D_38") (pintype "bidirectional"))
      (node (ref "U2") (pin "B36") (pinfunction "GPIO29(USB_HS_D_-)_B36") (pintype "bidirectional"))
      (node (ref "U2") (pin "B38") (pinfunction "+3V3_D_B38") (pintype "bidirectional"))
      (node (ref "U4") (pin "36") (pinfunction "GPIO29(USB_HS_D_-)_36") (pintype "bidirectional"))
      (node (ref "U4") (pin "38") (pinfunction "+3V3_D_38") (pintype "bidirectional"))
      (node (ref "U4") (pin "B36") (pinfunction "GPIO29(USB_HS_D_-)_B36") (pintype "bidirectional"))
      (node (ref "U4") (pin "B38") (pinfunction "+3V3_D_B38") (pintype "bidirectional"))
    )
    (net (code "265") (name "SCLK_2") (class "Default")
      (node (ref "U10") (pin "9") (pinfunction "GPIO8(SPI1_SCK)_9") (pintype "bidirectional"))
      (node (ref "U10") (pin "B9") (pinfunction "GPIO8(SPI1_SCK)_B9") (pintype "bidirectional"))
      (node (ref "U11") (pin "9") (pinfunction "GPIO8(SPI1_SCK)_9") (pintype "bidirectional"))
      (node (ref "U11") (pin "B9") (pinfunction "GPIO8(SPI1_SCK)_B9") (pintype "bidirectional"))
      (node (ref "U2") (pin "9") (pinfunction "GPIO8(SPI1_SCK)_9") (pintype "bidirectional"))
      (node (ref "U2") (pin "B9") (pinfunction "GPIO8(SPI1_SCK)_B9") (pintype "bidirectional"))
      (node (ref "U3") (pin "9") (pinfunction "GPIO8(SPI1_SCK)_9") (pintype "bidirectional"))
      (node (ref "U3") (pin "B9") (pinfunction "GPIO8(SPI1_SCK)_B9") (pintype "bidirectional"))
      (node (ref "U4") (pin "9") (pinfunction "GPIO8(SPI1_SCK)_9") (pintype "bidirectional"))
      (node (ref "U4") (pin "B9") (pinfunction "GPIO8(SPI1_SCK)_B9") (pintype "bidirectional"))
      (node (ref "U5") (pin "9") (pinfunction "GPIO8(SPI1_SCK)_9") (pintype "bidirectional"))
      (node (ref "U5") (pin "B9") (pinfunction "GPIO8(SPI1_SCK)_B9") (pintype "bidirectional"))
      (node (ref "U6") (pin "9") (pinfunction "GPIO8(SPI1_SCK)_9") (pintype "bidirectional"))
      (node (ref "U6") (pin "B9") (pinfunction "GPIO8(SPI1_SCK)_B9") (pintype "bidirectional"))
      (node (ref "U7") (pin "9") (pinfunction "GPIO8(SPI1_SCK)_9") (pintype "bidirectional"))
      (node (ref "U7") (pin "B9") (pinfunction "GPIO8(SPI1_SCK)_B9") (pintype "bidirectional"))
      (node (ref "U8") (pin "9") (pinfunction "GPIO8(SPI1_SCK)_9") (pintype "bidirectional"))
      (node (ref "U8") (pin "B9") (pinfunction "GPIO8(SPI1_SCK)_B9") (pintype "bidirectional"))
      (node (ref "U9") (pin "9") (pinfunction "GPIO8(SPI1_SCK)_9") (pintype "bidirectional"))
      (node (ref "U9") (pin "B9") (pinfunction "GPIO8(SPI1_SCK)_B9") (pintype "bidirectional"))
      (node (ref "X1") (pin "10") (pinfunction "KL_10") (pintype "passive"))
    )
    (net (code "266") (name "SD_CLK") (class "Default")
      (node (ref "R32") (pin "1") (pinfunction "1_1") (pintype "passive"))
      (node (ref "U7") (pin "7") (pinfunction "GPIO6(SDMMC1_CK)_7") (pintype "bidirectional"))
      (node (ref "U7") (pin "B7") (pinfunction "GPIO6(SDMMC1_CK)_B7") (pintype "bidirectional"))
    )
    (net (code "267") (name "SD_CMD") (class "Default")
      (node (ref "R31") (pin "1") (pinfunction "1_1") (pintype "passive"))
      (node (ref "R95") (pin "1") (pinfunction "1_1") (pintype "passive"))
      (node (ref "U7") (pin "6") (pinfunction "GPIO5(SDMMC1_CMD)_6") (pintype "bidirectional"))
      (node (ref "U7") (pin "B6") (pinfunction "GPIO5(SDMMC1_CMD)_B6") (pintype "bidirectional"))
    )
    (net (code "268") (name "SD_DAT0") (class "Default")
      (node (ref "R33") (pin "1") (pinfunction "1_1") (pintype "passive"))
      (node (ref "R94") (pin "1") (pinfunction "1_1") (pintype "passive"))
      (node (ref "U7") (pin "5") (pinfunction "GPIO4(SDMMC1_D0)_5") (pintype "bidirectional"))
      (node (ref "U7") (pin "B5") (pinfunction "GPIO4(SDMMC1_D0)_B5") (pintype "bidirectional"))
    )
    (net (code "269") (name "SD_DAT1") (class "Default")
      (node (ref "R34") (pin "1") (pinfunction "1_1") (pintype "passive"))
      (node (ref "R93") (pin "1") (pinfunction "1_1") (pintype "passive"))
      (node (ref "U7") (pin "4") (pinfunction "GPIO3(SDMMC1_D1)_4") (pintype "bidirectional"))
      (node (ref "U7") (pin "B4") (pinfunction "GPIO3(SDMMC1_D1)_B4") (pintype "bidirectional"))
    )
    (net (code "270") (name "SD_DAT2") (class "Default")
      (node (ref "R29") (pin "1") (pinfunction "1_1") (pintype "passive"))
      (node (ref "R97") (pin "1") (pinfunction "1_1") (pintype "passive"))
      (node (ref "U7") (pin "3") (pinfunction "GPIO2(SDMMC1_D2)_3") (pintype "bidirectional"))
      (node (ref "U7") (pin "B3") (pinfunction "GPIO2(SDMMC1_D2)_B3") (pintype "bidirectional"))
    )
    (net (code "271") (name "SD_DAT3") (class "Default")
      (node (ref "R30") (pin "1") (pinfunction "1_1") (pintype "passive"))
      (node (ref "R96") (pin "1") (pinfunction "1_1") (pintype "passive"))
      (node (ref "U7") (pin "2") (pinfunction "GPIO1(SDMMC1_D3)_2") (pintype "bidirectional"))
      (node (ref "U7") (pin "B2") (pinfunction "GPIO1(SDMMC1_D3)_B2") (pintype "bidirectional"))
    )
    (net (code "272") (name "SPI6_CLK") (class "Default")
      (node (ref "U10") (pin "29") (pinfunction "GPIO22(ADC7/DAC2)_29") (pintype "bidirectional"))
      (node (ref "U10") (pin "B29") (pinfunction "GPIO22(ADC7/DAC2)_B29") (pintype "bidirectional"))
      (node (ref "U11") (pin "29") (pinfunction "GPIO22(ADC7/DAC2)_29") (pintype "bidirectional"))
      (node (ref "U11") (pin "B29") (pinfunction "GPIO22(ADC7/DAC2)_B29") (pintype "bidirectional"))
      (node (ref "U2") (pin "29") (pinfunction "GPIO22(ADC7/DAC2)_29") (pintype "bidirectional"))
      (node (ref "U2") (pin "B29") (pinfunction "GPIO22(ADC7/DAC2)_B29") (pintype "bidirectional"))
      (node (ref "U3") (pin "29") (pinfunction "GPIO22(ADC7/DAC2)_29") (pintype "bidirectional"))
      (node (ref "U3") (pin "B29") (pinfunction "GPIO22(ADC7/DAC2)_B29") (pintype "bidirectional"))
      (node (ref "U4") (pin "29") (pinfunction "GPIO22(ADC7/DAC2)_29") (pintype "bidirectional"))
      (node (ref "U4") (pin "B29") (pinfunction "GPIO22(ADC7/DAC2)_B29") (pintype "bidirectional"))
      (node (ref "U5") (pin "29") (pinfunction "GPIO22(ADC7/DAC2)_29") (pintype "bidirectional"))
      (node (ref "U5") (pin "B29") (pinfunction "GPIO22(ADC7/DAC2)_B29") (pintype "bidirectional"))
      (node (ref "U6") (pin "29") (pinfunction "GPIO22(ADC7/DAC2)_29") (pintype "bidirectional"))
      (node (ref "U6") (pin "B29") (pinfunction "GPIO22(ADC7/DAC2)_B29") (pintype "bidirectional"))
      (node (ref "U7") (pin "29") (pinfunction "GPIO22(ADC7/DAC2)_29") (pintype "bidirectional"))
      (node (ref "U7") (pin "B29") (pinfunction "GPIO22(ADC7/DAC2)_B29") (pintype "bidirectional"))
      (node (ref "U8") (pin "29") (pinfunction "GPIO22(ADC7/DAC2)_29") (pintype "bidirectional"))
      (node (ref "U8") (pin "B29") (pinfunction "GPIO22(ADC7/DAC2)_B29") (pintype "bidirectional"))
      (node (ref "U9") (pin "29") (pinfunction "GPIO22(ADC7/DAC2)_29") (pintype "bidirectional"))
      (node (ref "U9") (pin "B29") (pinfunction "GPIO22(ADC7/DAC2)_B29") (pintype "bidirectional"))
      (node (ref "X1") (pin "6") (pinfunction "KL_6") (pintype "passive"))
    )
    (net (code "273") (name "SPI6_MOSI") (class "Default")
      (node (ref "U10") (pin "25") (pinfunction "GPIO18(ADC3)_25") (pintype "bidirectional"))
      (node (ref "U10") (pin "B25") (pinfunction "GPIO18(ADC3)_B25") (pintype "bidirectional"))
      (node (ref "U11") (pin "25") (pinfunction "GPIO18(ADC3)_25") (pintype "bidirectional"))
      (node (ref "U11") (pin "B25") (pinfunction "GPIO18(ADC3)_B25") (pintype "bidirectional"))
      (node (ref "U2") (pin "25") (pinfunction "GPIO18(ADC3)_25") (pintype "bidirectional"))
      (node (ref "U2") (pin "B25") (pinfunction "GPIO18(ADC3)_B25") (pintype "bidirectional"))
      (node (ref "U3") (pin "25") (pinfunction "GPIO18(ADC3)_25") (pintype "bidirectional"))
      (node (ref "U3") (pin "B25") (pinfunction "GPIO18(ADC3)_B25") (pintype "bidirectional"))
      (node (ref "U4") (pin "25") (pinfunction "GPIO18(ADC3)_25") (pintype "bidirectional"))
      (node (ref "U4") (pin "B25") (pinfunction "GPIO18(ADC3)_B25") (pintype "bidirectional"))
      (node (ref "U5") (pin "25") (pinfunction "GPIO18(ADC3)_25") (pintype "bidirectional"))
      (node (ref "U5") (pin "B25") (pinfunction "GPIO18(ADC3)_B25") (pintype "bidirectional"))
      (node (ref "U6") (pin "25") (pinfunction "GPIO18(ADC3)_25") (pintype "bidirectional"))
      (node (ref "U6") (pin "B25") (pinfunction "GPIO18(ADC3)_B25") (pintype "bidirectional"))
      (node (ref "U7") (pin "25") (pinfunction "GPIO18(ADC3)_25") (pintype "bidirectional"))
      (node (ref "U7") (pin "B25") (pinfunction "GPIO18(ADC3)_B25") (pintype "bidirectional"))
      (node (ref "U8") (pin "25") (pinfunction "GPIO18(ADC3)_25") (pintype "bidirectional"))
      (node (ref "U8") (pin "B25") (pinfunction "GPIO18(ADC3)_B25") (pintype "bidirectional"))
      (node (ref "U9") (pin "25") (pinfunction "GPIO18(ADC3)_25") (pintype "bidirectional"))
      (node (ref "U9") (pin "B25") (pinfunction "GPIO18(ADC3)_B25") (pintype "bidirectional"))
      (node (ref "X1") (pin "8") (pinfunction "KL_8") (pintype "passive"))
    )
    (net (code "274") (name "SPI6_NSS") (class "Default")
      (node (ref "U10") (pin "30") (pinfunction "GPIO23(ADC8/DAC1)_30") (pintype "bidirectional"))
      (node (ref "U10") (pin "B30") (pinfunction "GPIO23(ADC8/DAC1)_B30") (pintype "bidirectional"))
      (node (ref "U11") (pin "30") (pinfunction "GPIO23(ADC8/DAC1)_30") (pintype "bidirectional"))
      (node (ref "U11") (pin "B30") (pinfunction "GPIO23(ADC8/DAC1)_B30") (pintype "bidirectional"))
      (node (ref "U2") (pin "30") (pinfunction "GPIO23(ADC8/DAC1)_30") (pintype "bidirectional"))
      (node (ref "U2") (pin "B30") (pinfunction "GPIO23(ADC8/DAC1)_B30") (pintype "bidirectional"))
      (node (ref "U3") (pin "30") (pinfunction "GPIO23(ADC8/DAC1)_30") (pintype "bidirectional"))
      (node (ref "U3") (pin "B30") (pinfunction "GPIO23(ADC8/DAC1)_B30") (pintype "bidirectional"))
      (node (ref "U4") (pin "30") (pinfunction "GPIO23(ADC8/DAC1)_30") (pintype "bidirectional"))
      (node (ref "U4") (pin "B30") (pinfunction "GPIO23(ADC8/DAC1)_B30") (pintype "bidirectional"))
      (node (ref "U5") (pin "30") (pinfunction "GPIO23(ADC8/DAC1)_30") (pintype "bidirectional"))
      (node (ref "U5") (pin "B30") (pinfunction "GPIO23(ADC8/DAC1)_B30") (pintype "bidirectional"))
      (node (ref "U6") (pin "30") (pinfunction "GPIO23(ADC8/DAC1)_30") (pintype "bidirectional"))
      (node (ref "U6") (pin "B30") (pinfunction "GPIO23(ADC8/DAC1)_B30") (pintype "bidirectional"))
      (node (ref "U7") (pin "30") (pinfunction "GPIO23(ADC8/DAC1)_30") (pintype "bidirectional"))
      (node (ref "U7") (pin "B30") (pinfunction "GPIO23(ADC8/DAC1)_B30") (pintype "bidirectional"))
      (node (ref "U8") (pin "30") (pinfunction "GPIO23(ADC8/DAC1)_30") (pintype "bidirectional"))
      (node (ref "U8") (pin "B30") (pinfunction "GPIO23(ADC8/DAC1)_B30") (pintype "bidirectional"))
      (node (ref "U9") (pin "30") (pinfunction "GPIO23(ADC8/DAC1)_30") (pintype "bidirectional"))
      (node (ref "U9") (pin "B30") (pinfunction "GPIO23(ADC8/DAC1)_B30") (pintype "bidirectional"))
      (node (ref "X1") (pin "5") (pinfunction "KL_5") (pintype "passive"))
    )
    (net (code "275") (name "SS_2") (class "Default")
      (node (ref "U10") (pin "8") (pinfunction "GPIO7(SPI1_NSS)_8") (pintype "bidirectional"))
      (node (ref "U10") (pin "B8") (pinfunction "GPIO7(SPI1_NSS)_B8") (pintype "bidirectional"))
      (node (ref "U11") (pin "8") (pinfunction "GPIO7(SPI1_NSS)_8") (pintype "bidirectional"))
      (node (ref "U11") (pin "B8") (pinfunction "GPIO7(SPI1_NSS)_B8") (pintype "bidirectional"))
      (node (ref "U2") (pin "8") (pinfunction "GPIO7(SPI1_NSS)_8") (pintype "bidirectional"))
      (node (ref "U2") (pin "B8") (pinfunction "GPIO7(SPI1_NSS)_B8") (pintype "bidirectional"))
      (node (ref "U3") (pin "8") (pinfunction "GPIO7(SPI1_NSS)_8") (pintype "bidirectional"))
      (node (ref "U3") (pin "B8") (pinfunction "GPIO7(SPI1_NSS)_B8") (pintype "bidirectional"))
      (node (ref "U4") (pin "8") (pinfunction "GPIO7(SPI1_NSS)_8") (pintype "bidirectional"))
      (node (ref "U4") (pin "B8") (pinfunction "GPIO7(SPI1_NSS)_B8") (pintype "bidirectional"))
      (node (ref "U5") (pin "8") (pinfunction "GPIO7(SPI1_NSS)_8") (pintype "bidirectional"))
      (node (ref "U5") (pin "B8") (pinfunction "GPIO7(SPI1_NSS)_B8") (pintype "bidirectional"))
      (node (ref "U6") (pin "8") (pinfunction "GPIO7(SPI1_NSS)_8") (pintype "bidirectional"))
      (node (ref "U6") (pin "B8") (pinfunction "GPIO7(SPI1_NSS)_B8") (pintype "bidirectional"))
      (node (ref "U7") (pin "8") (pinfunction "GPIO7(SPI1_NSS)_8") (pintype "bidirectional"))
      (node (ref "U7") (pin "B8") (pinfunction "GPIO7(SPI1_NSS)_B8") (pintype "bidirectional"))
      (node (ref "U8") (pin "8") (pinfunction "GPIO7(SPI1_NSS)_8") (pintype "bidirectional"))
      (node (ref "U8") (pin "B8") (pinfunction "GPIO7(SPI1_NSS)_B8") (pintype "bidirectional"))
      (node (ref "U9") (pin "8") (pinfunction "GPIO7(SPI1_NSS)_8") (pintype "bidirectional"))
      (node (ref "U9") (pin "B8") (pinfunction "GPIO7(SPI1_NSS)_B8") (pintype "bidirectional"))
      (node (ref "X1") (pin "9") (pinfunction "KL_9") (pintype "passive"))
    )
    (net (code "276") (name "unconnected-(PS1-NC-Pad3)") (class "Default")
      (node (ref "PS1") (pin "3") (pinfunction "NC_3") (pintype "no_connect"))
    )
    (net (code "277") (name "unconnected-(PS1-NC-Pad5)") (class "Default")
      (node (ref "PS1") (pin "5") (pinfunction "NC_5") (pintype "no_connect"))
    )
    (net (code "278") (name "unconnected-(X1E-KL-Pad13)") (class "Default")
      (node (ref "X1") (pin "13") (pinfunction "KL_13") (pintype "passive"))
    )
    (net (code "279") (name "unconnected-(X1F-KL-Pad14)") (class "Default")
      (node (ref "X1") (pin "14") (pinfunction "KL_14") (pintype "passive"))
    )
    (net (code "280") (name "unconnected-(X1G-KL-Pad15)") (class "Default")
      (node (ref "X1") (pin "15") (pinfunction "KL_15") (pintype "passive"))
    )
    (net (code "281") (name "unconnected-(X1H-KL-Pad16)") (class "Default")
      (node (ref "X1") (pin "16") (pinfunction "KL_16") (pintype "passive"))
    )
    (net (code "282") (name "unconnected-(X1N-KL-Pad7)") (class "Default")
      (node (ref "X1") (pin "7") (pinfunction "KL_7") (pintype "passive"))
    )
  )
)
